# base-32-bit.net
KiCad netlist of a schematic drawn in Altium Designer
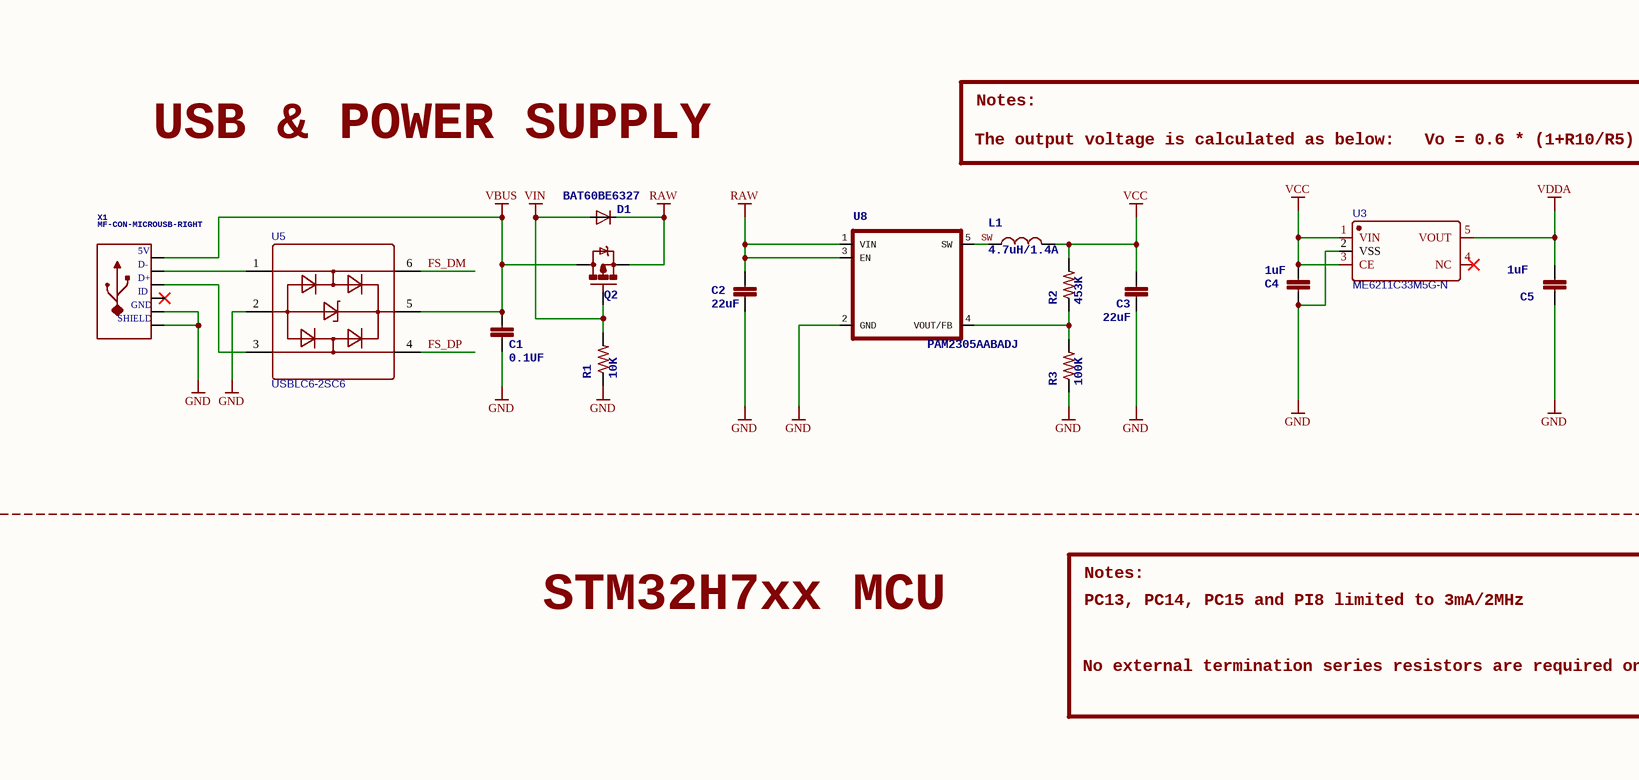
[diagram p0: base-32-bit.SchDoc, top left]
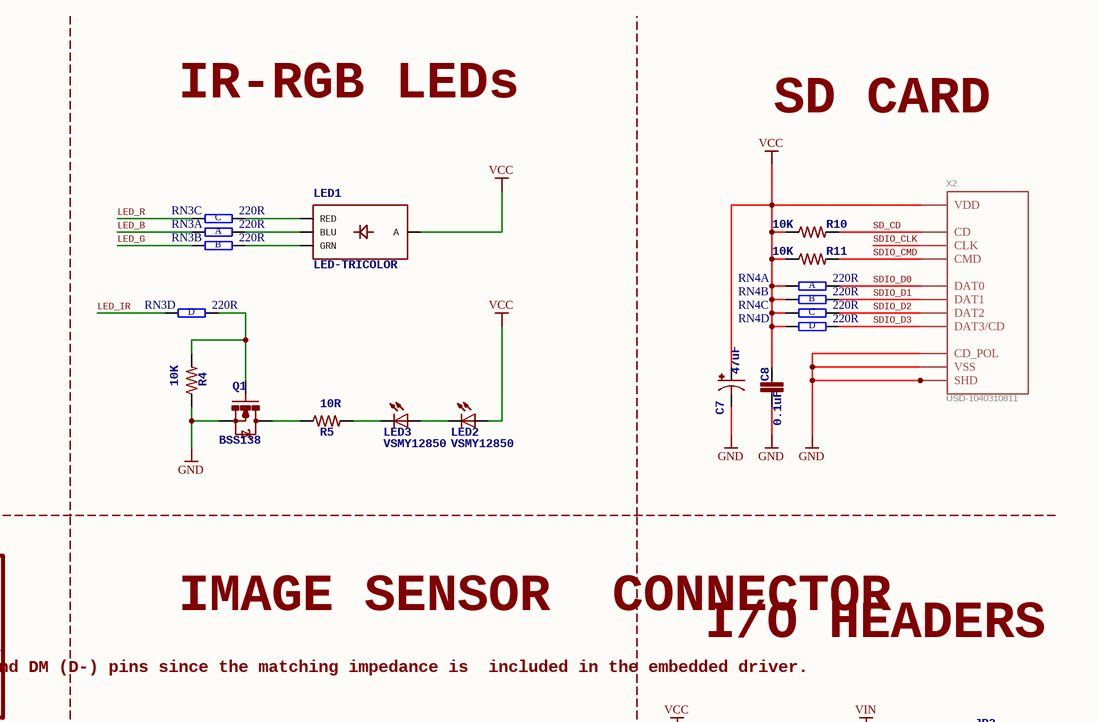
[diagram p1: base-32-bit.SchDoc, top right]
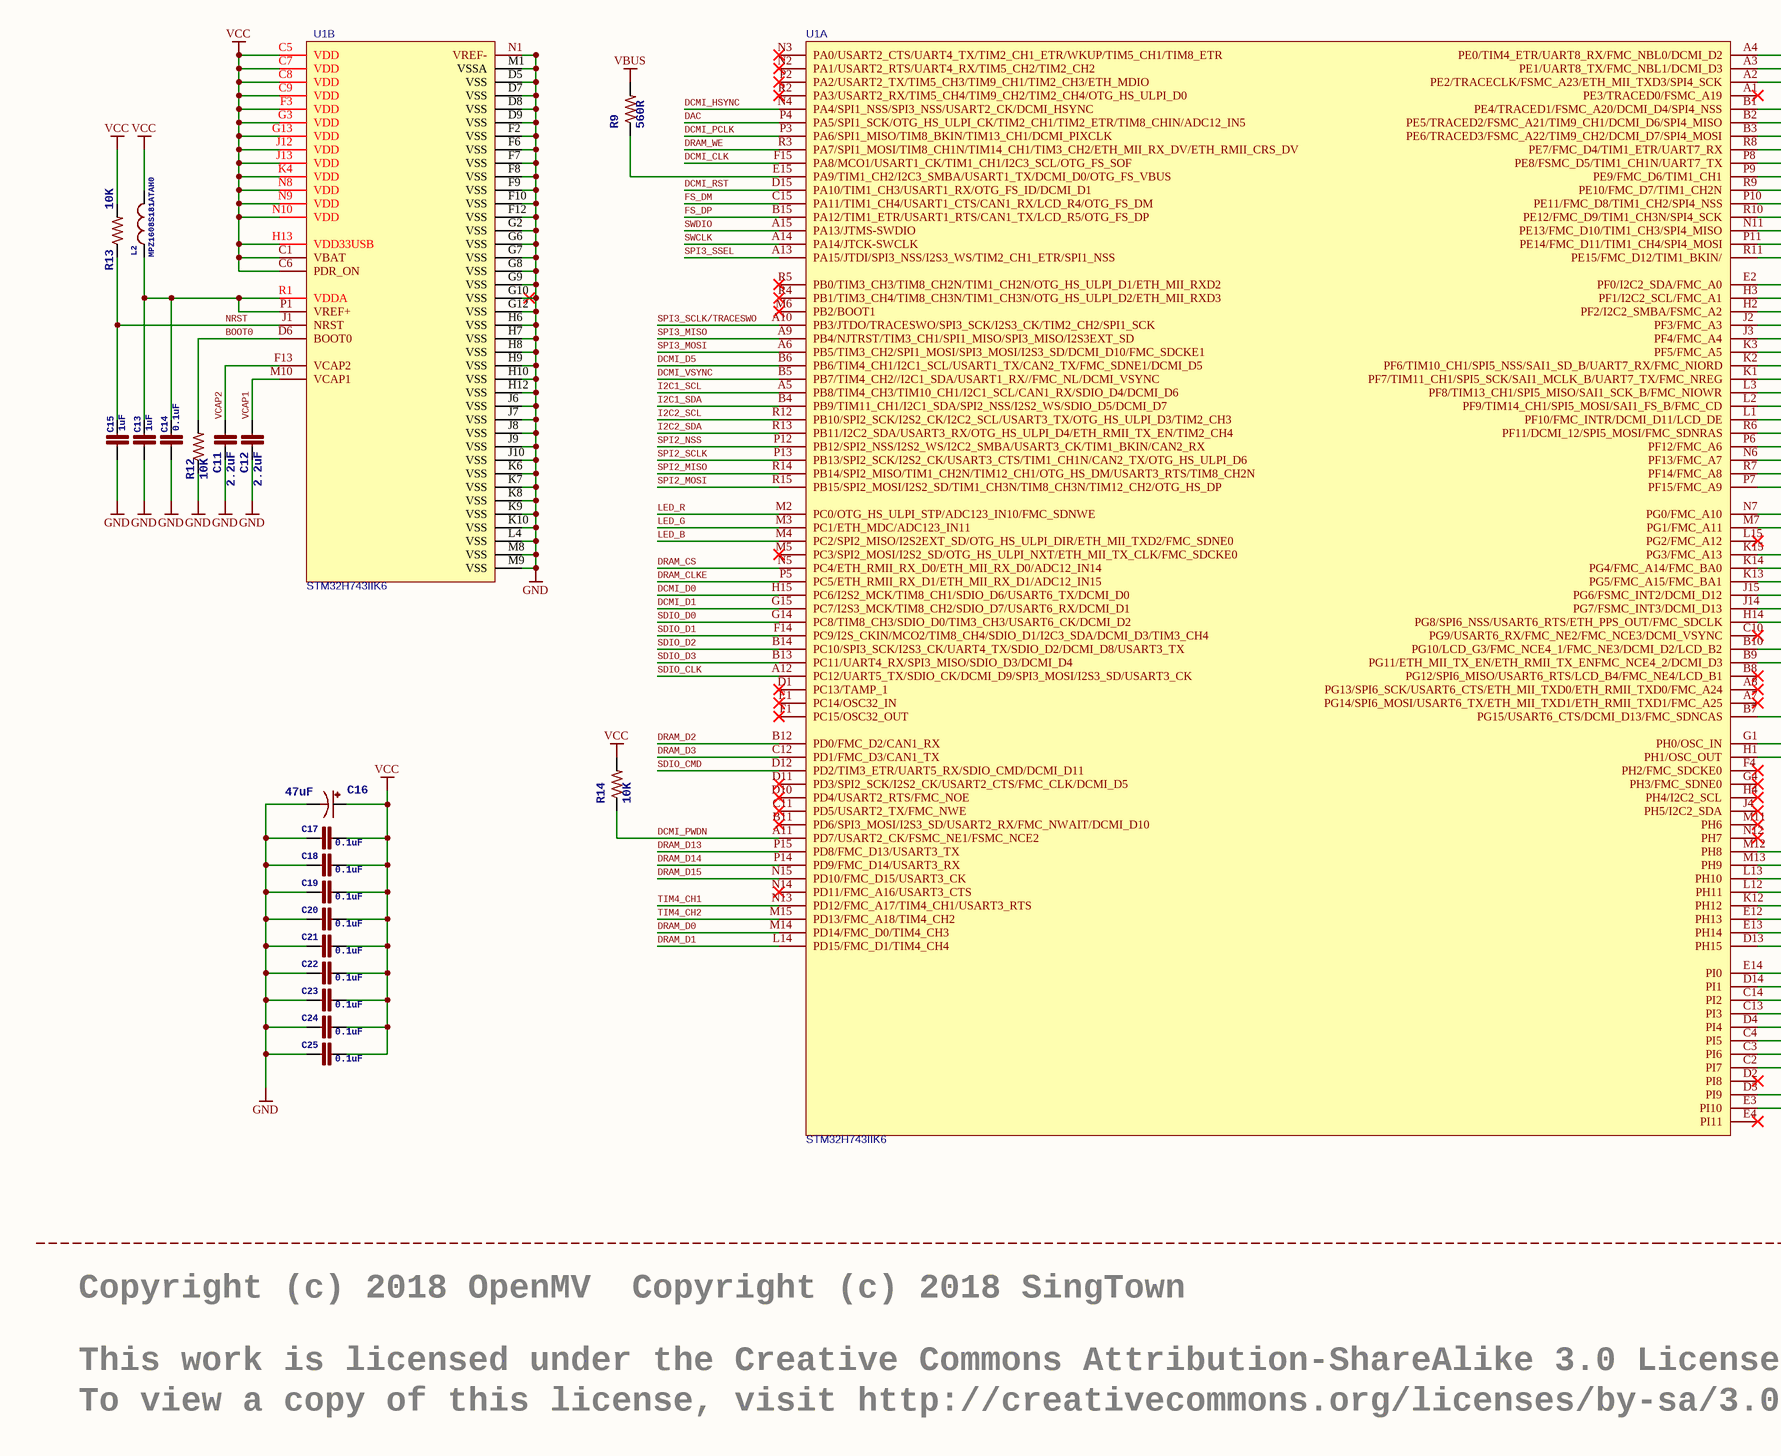
[diagram p2: base-32-bit.SchDoc, bottom left]
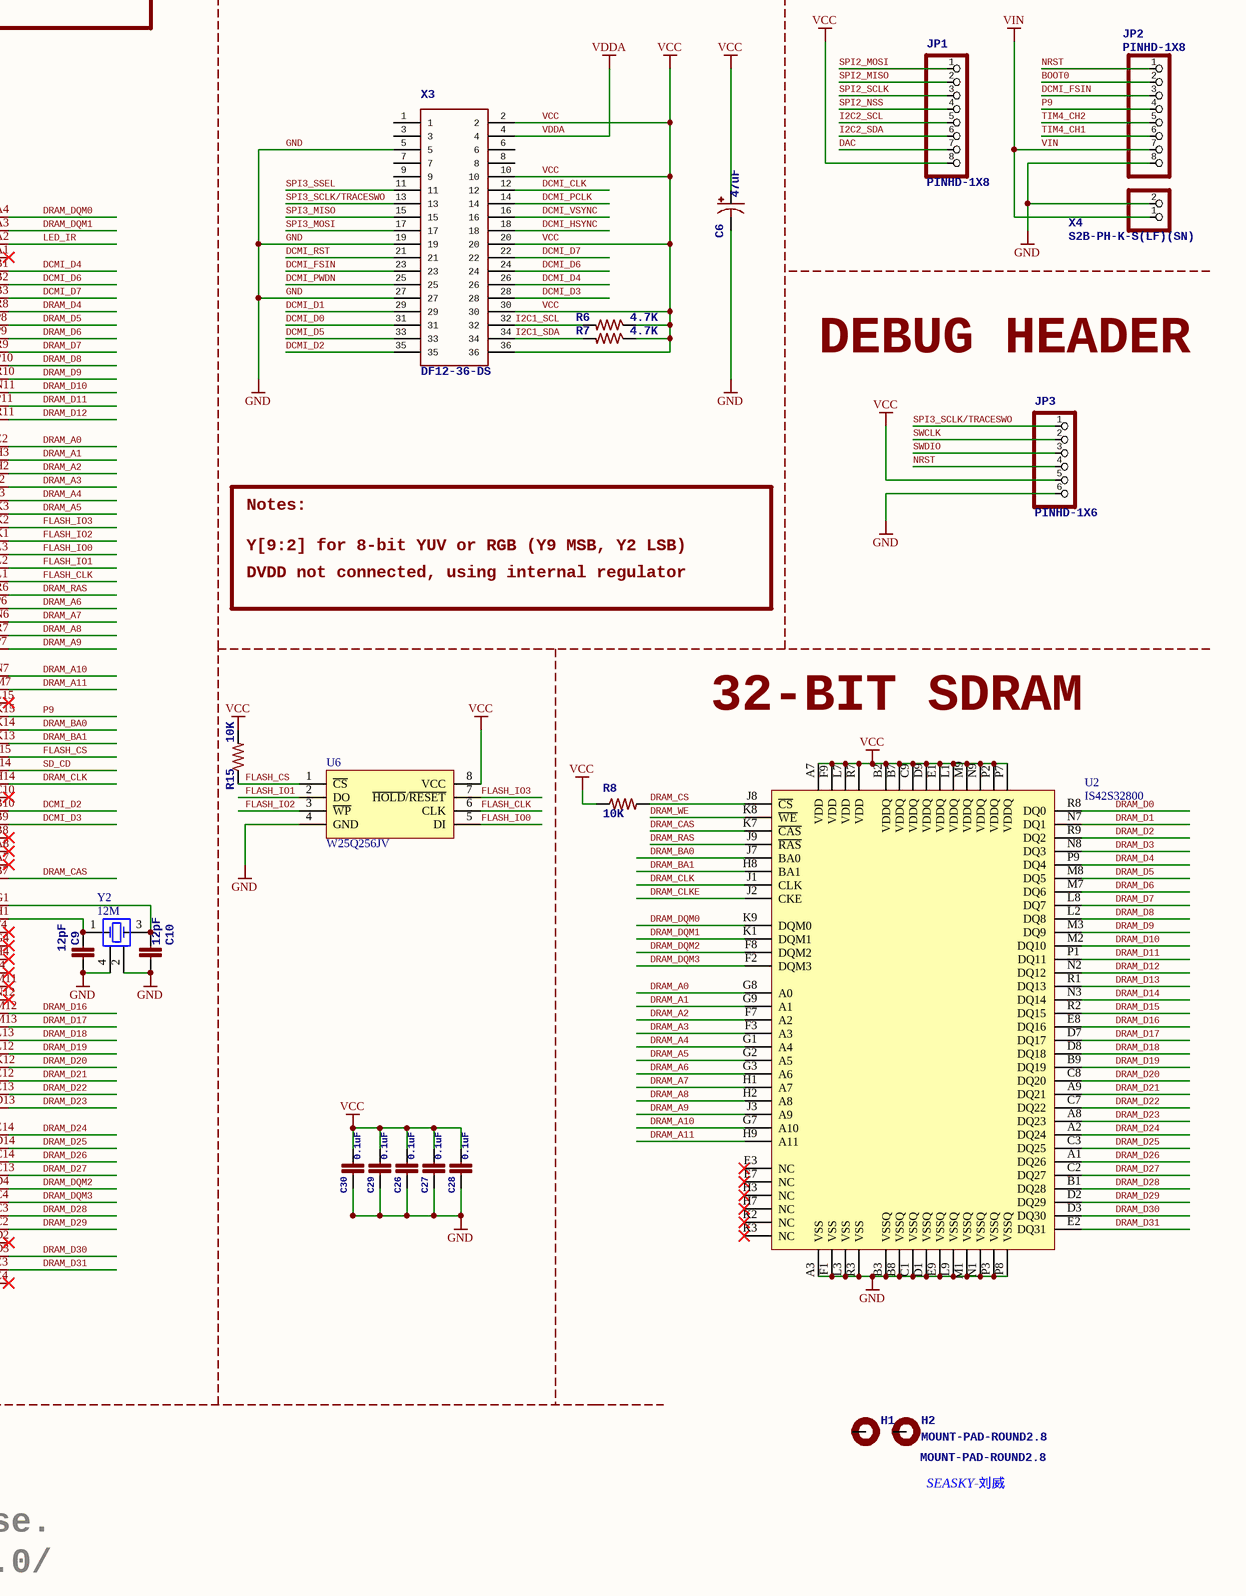
[diagram p3: base-32-bit.SchDoc, bottom right]

(export (version "E")
  (design (tool "Eeschema 10.0.6"))
  (components
    (comp (ref "C1")
      (value "0.1UF")
      (footprint "C0603")
      (description "CapacitorStandard 0603 ceramic capacitor, and 0.1\" leaded capacitor.")
      (libsource (lib "sfe") (part "CAP0805"))
    )
    (comp (ref "C2")
      (value "22uF")
      (footprint "0805")
      (description "CapacitorStandard 0603 ceramic capacitor, and 0.1\" leaded capacitor.")
      (libsource (lib "sfe") (part "CAP0805"))
    )
    (comp (ref "C3")
      (value "22uF")
      (footprint "0805")
      (description "CapacitorStandard 0603 ceramic capacitor, and 0.1\" leaded capacitor.")
      (libsource (lib "sfe") (part "CAP0805"))
    )
    (comp (ref "C4")
      (value "1uF")
      (footprint "0805")
      (description "CapacitorStandard 0603 ceramic capacitor, and 0.1\" leaded capacitor.")
      (libsource (lib "sfe") (part "CAP0805"))
    )
    (comp (ref "C5")
      (value "1uF")
      (footprint "0805")
      (description "CapacitorStandard 0603 ceramic capacitor, and 0.1\" leaded capacitor.")
      (libsource (lib "sfe") (part "CAP0805"))
    )
    (comp (ref "C6") (value "47uF") (footprint "EIA3216") (libsource (lib "") (part "CAP_POL1206_1")))
    (comp (ref "C7") (value "47uF") (footprint "EIA3216") (libsource (lib "") (part "CAP_POL1206_1")))
    (comp (ref "C8")
      (value "0.1uF")
      (footprint "0603-CAP")
      (description "CapacitorStandard 0603 ceramic capacitor, and 0.1\" leaded capacitor.")
      (libsource (lib "") (part "CAP0603-CAP_1"))
    )
    (comp (ref "C9")
      (value "12pF")
      (footprint "0603-CAP")
      (description "CapacitorStandard 0603 ceramic capacitor, and 0.1\" leaded capacitor.")
      (libsource (lib "sfe") (part "CAP0603-CAP"))
    )
    (comp (ref "C10")
      (value "12pF")
      (footprint "0603-CAP")
      (description "CapacitorStandard 0603 ceramic capacitor, and 0.1\" leaded capacitor.")
      (libsource (lib "sfe") (part "CAP0603-CAP"))
    )
    (comp (ref "C11")
      (value "2.2uF")
      (footprint "C0402")
      (description "CapacitorStandard 0603 ceramic capacitor, and 0.1\" leaded capacitor.")
      (libsource (lib "") (part "CAP0603-CAP_1"))
    )
    (comp (ref "C12")
      (value "2.2uF")
      (footprint "C0402")
      (description "CapacitorStandard 0603 ceramic capacitor, and 0.1\" leaded capacitor.")
      (libsource (lib "") (part "CAP0603-CAP_1"))
    )
    (comp (ref "C13")
      (value "1uF")
      (footprint "C0402")
      (description "CapacitorStandard 0603 ceramic capacitor, and 0.1\" leaded capacitor.")
      (libsource (lib "") (part "CAP0402-CAP_1"))
    )
    (comp (ref "C14")
      (value "0.1uF")
      (footprint "C0402")
      (description "CapacitorStandard 0603 ceramic capacitor, and 0.1\" leaded capacitor.")
      (libsource (lib "") (part "CAP0402-CAP_1"))
    )
    (comp (ref "C15")
      (value "1uF")
      (footprint "C0402")
      (description "CapacitorStandard 0603 ceramic capacitor, and 0.1\" leaded capacitor.")
      (libsource (lib "") (part "CAP0402-CAP_1"))
    )
    (comp (ref "C16") (value "47uF") (footprint "EIA3216") (libsource (lib "sfe") (part "CAP_POL1206")))
    (comp (ref "C17")
      (value "0.1uF")
      (footprint "C0402")
      (description "CapacitorStandard 0603 ceramic capacitor, and 0.1\" leaded capacitor.")
      (libsource (lib "sfe") (part "CAP0402-CAP"))
    )
    (comp (ref "C18")
      (value "0.1uF")
      (footprint "C0402")
      (description "CapacitorStandard 0603 ceramic capacitor, and 0.1\" leaded capacitor.")
      (libsource (lib "sfe") (part "CAP0402-CAP"))
    )
    (comp (ref "C19")
      (value "0.1uF")
      (footprint "C0402")
      (description "CapacitorStandard 0603 ceramic capacitor, and 0.1\" leaded capacitor.")
      (libsource (lib "sfe") (part "CAP0402-CAP"))
    )
    (comp (ref "C20")
      (value "0.1uF")
      (footprint "C0402")
      (description "CapacitorStandard 0603 ceramic capacitor, and 0.1\" leaded capacitor.")
      (libsource (lib "sfe") (part "CAP0402-CAP"))
    )
    (comp (ref "C21")
      (value "0.1uF")
      (footprint "C0402")
      (description "CapacitorStandard 0603 ceramic capacitor, and 0.1\" leaded capacitor.")
      (libsource (lib "sfe") (part "CAP0402-CAP"))
    )
    (comp (ref "C22")
      (value "0.1uF")
      (footprint "C0402")
      (description "CapacitorStandard 0603 ceramic capacitor, and 0.1\" leaded capacitor.")
      (libsource (lib "sfe") (part "CAP0402-CAP"))
    )
    (comp (ref "C23")
      (value "0.1uF")
      (footprint "C0402")
      (description "CapacitorStandard 0603 ceramic capacitor, and 0.1\" leaded capacitor.")
      (libsource (lib "sfe") (part "CAP0402-CAP"))
    )
    (comp (ref "C24")
      (value "0.1uF")
      (footprint "C0402")
      (description "CapacitorStandard 0603 ceramic capacitor, and 0.1\" leaded capacitor.")
      (libsource (lib "sfe") (part "CAP0402-CAP"))
    )
    (comp (ref "C25")
      (value "0.1uF")
      (footprint "C0402")
      (description "CapacitorStandard 0603 ceramic capacitor, and 0.1\" leaded capacitor.")
      (libsource (lib "sfe") (part "CAP0402-CAP"))
    )
    (comp (ref "C26")
      (value "0.1uF")
      (footprint "C0402")
      (description "CapacitorStandard 0603 ceramic capacitor, and 0.1\" leaded capacitor.")
      (libsource (lib "") (part "CAP0402-CAP_1"))
    )
    (comp (ref "C27")
      (value "0.1uF")
      (footprint "C0402")
      (description "CapacitorStandard 0603 ceramic capacitor, and 0.1\" leaded capacitor.")
      (libsource (lib "") (part "CAP0402-CAP_1"))
    )
    (comp (ref "C28")
      (value "0.1uF")
      (footprint "C0402")
      (description "CapacitorStandard 0603 ceramic capacitor, and 0.1\" leaded capacitor.")
      (libsource (lib "") (part "CAP0402-CAP_1"))
    )
    (comp (ref "C29")
      (value "0.1uF")
      (footprint "C0402")
      (description "CapacitorStandard 0603 ceramic capacitor, and 0.1\" leaded capacitor.")
      (libsource (lib "") (part "CAP0402-CAP_1"))
    )
    (comp (ref "C30")
      (value "0.1uF")
      (footprint "C0402")
      (description "CapacitorStandard 0603 ceramic capacitor, and 0.1\" leaded capacitor.")
      (libsource (lib "") (part "CAP0402-CAP_1"))
    )
    (comp (ref "D1") (value "BAT60BE6327") (footprint "SOD-323") (libsource (lib "sfe") (part "DIODESOD")))
    (comp (ref "H1")
      (value "MOUNT-PAD-ROUND2.8")
      (footprint "2,8-PAD")
      (description "MOUNTING PAD, round")
      (libsource (lib "holes") (part "MOUNT-PAD-ROUND2.8"))
    )
    (comp (ref "H2")
      (value "MOUNT-PAD-ROUND2.8")
      (footprint "2,8-PAD")
      (description "MOUNTING PAD, round")
      (libsource (lib "holes") (part "MOUNT-PAD-ROUND2.8"))
    )
    (comp (ref "JP1")
      (value "PINHD-1X8")
      (footprint "1X08")
      (description "PIN HEADER")
      (libsource (lib "pinhead") (part "PINHD-1X8"))
    )
    (comp (ref "JP2")
      (value "PINHD-1X8")
      (footprint "1X08")
      (description "PIN HEADER")
      (libsource (lib "pinhead") (part "PINHD-1X8"))
    )
    (comp (ref "JP3")
      (value "PINHD-1X6")
      (footprint "1X06")
      (description "PIN HEADER")
      (libsource (lib "pinhead") (part "PINHD-1X6"))
    )
    (comp (ref "L1") (value "4.7uH/1.4A") (footprint "1007") (libsource (lib "sfe") (part "INDUCTOR1007")))
    (comp (ref "L2")
      (value "MPZ1608S181ATAH0")
      (footprint "0603")
      (libsource (lib "sfe") (part "INDUCTOR0603"))
    )
    (comp (ref "LED1")
      (value "LED-TRICOLOR")
      (footprint "LED-TRICOLOR-SMD")
      (libsource (lib "sfe") (part "LED-TRICOLOR"))
    )
    (comp (ref "LED2") (value "VSMY12850") (footprint "LED-1206") (libsource (lib "sfe") (part "LED1206")))
    (comp (ref "LED3") (value "VSMY12850") (footprint "LED-1206") (libsource (lib "sfe") (part "LED1206")))
    (comp (ref "Q1")
      (value "BSS138")
      (footprint "SOT23-3")
      (libsource (lib "sfe") (part "MOSFET-NCHANNELSMD"))
    )
    (comp (ref "Q2")
      (value "Si2301BDS")
      (footprint "SOT23-3")
      (libsource (lib "sfe") (part "MOSFET-PCHANNELSMD"))
    )
    (comp (ref "R1")
      (value "10K")
      (footprint "R0603")
      (description "ResistorBasic schematic elements and footprints for 0603, 1206, and PTH resistors.")
      (libsource (lib "sfe") (part "RESISTOR0603-RES"))
    )
    (comp (ref "R2")
      (value "453K")
      (footprint "R0603")
      (description "ResistorBasic schematic elements and footprints for 0603, 1206, and PTH resistors.")
      (libsource (lib "sfe") (part "RESISTOR0603-RES"))
    )
    (comp (ref "R3")
      (value "100K")
      (footprint "R0603")
      (description "ResistorBasic schematic elements and footprints for 0603, 1206, and PTH resistors.")
      (libsource (lib "sfe") (part "RESISTOR0603-RES"))
    )
    (comp (ref "R4")
      (value "10K")
      (footprint "R0603")
      (description "ResistorBasic schematic elements and footprints for 0603, 1206, and PTH resistors.")
      (libsource (lib "sfe") (part "RESISTOR0603-RES"))
    )
    (comp (ref "R5")
      (value "10R")
      (footprint "R0603")
      (description "ResistorBasic schematic elements and footprints for 0603, 1206, and PTH resistors.")
      (libsource (lib "sfe") (part "RESISTOR0603-RES"))
    )
    (comp (ref "R6")
      (value "4.7K")
      (footprint "R0603")
      (description "ResistorBasic schematic elements and footprints for 0603, 1206, and PTH resistors.")
      (libsource (lib "sfe") (part "RESISTOR0603-RES"))
    )
    (comp (ref "R7")
      (value "4.7K")
      (footprint "R0603")
      (description "ResistorBasic schematic elements and footprints for 0603, 1206, and PTH resistors.")
      (libsource (lib "sfe") (part "RESISTOR0603-RES"))
    )
    (comp (ref "R8")
      (value "10K")
      (footprint "R0402")
      (description "ResistorBasic schematic elements and footprints for 0603, 1206, and PTH resistors.")
      (libsource (lib "sfe") (part "RESISTOR0402-RES"))
    )
    (comp (ref "R9")
      (value "560R")
      (footprint "R0603")
      (description "ResistorBasic schematic elements and footprints for 0603, 1206, and PTH resistors.")
      (libsource (lib "sfe") (part "RESISTOR0603-RES"))
    )
    (comp (ref "R10")
      (value "10K")
      (footprint "R0603")
      (description "ResistorBasic schematic elements and footprints for 0603, 1206, and PTH resistors.")
      (libsource (lib "sfe") (part "RESISTOR0603-RES"))
    )
    (comp (ref "R11")
      (value "10K")
      (footprint "R0603")
      (description "ResistorBasic schematic elements and footprints for 0603, 1206, and PTH resistors.")
      (libsource (lib "sfe") (part "RESISTOR0603-RES"))
    )
    (comp (ref "R12")
      (value "10K")
      (footprint "R0603")
      (description "ResistorBasic schematic elements and footprints for 0603, 1206, and PTH resistors.")
      (libsource (lib "sfe") (part "RESISTOR0603-RES"))
    )
    (comp (ref "R13")
      (value "10K")
      (footprint "R0402")
      (description "ResistorBasic schematic elements and footprints for 0603, 1206, and PTH resistors.")
      (libsource (lib "sfe") (part "RESISTOR0603-RES"))
    )
    (comp (ref "R14")
      (value "10K")
      (footprint "R0603")
      (description "ResistorBasic schematic elements and footprints for 0603, 1206, and PTH resistors.")
      (libsource (lib "sfe") (part "RESISTOR0603-RES"))
    )
    (comp (ref "R15")
      (value "10K")
      (footprint "R0603")
      (description "ResistorBasic schematic elements and footprints for 0603, 1206, and PTH resistors.")
      (libsource (lib "sfe") (part "RESISTOR0402-RES"))
    )
    (comp (ref "RN3")
      (value "220R")
      (footprint "RCA-8P4R-0402")
      (libsource (lib "Integrated_Library1") (part "排阻_4P"))
    )
    (comp (ref "RN4")
      (value "220R")
      (footprint "RCA-8P4R-0402")
      (libsource (lib "Integrated_Library1") (part "排阻_4P"))
    )
    (comp (ref "U1")
      (value "STM32H743IIK6")
      (footprint "UFBGA-201_L10.0-W10.0-P0.65-TL_STM32H743IIK6")
      (fields
        (field (name "BOM_SUPPLIER PART") "C129442")
        (field (name "SUBPART_NO") "2")
        (field (name "CONTRIBUTOR") "LCSC")
      )
      (libsource (lib "Integrated_Library1") (part "STM32H743IIK6"))
    )
    (comp (ref "U2")
      (value "IS42S32800")
      (footprint "BGA-90-8000X13000DE")
      (libsource (lib "Schlib1") (part "IS42S32800"))
    )
    (comp (ref "U3")
      (value "ME6211C33M5G-N")
      (footprint "SOT-23-5")
      (fields (field (name "BOM_SUPPLIER PART") "C82942"))
      (libsource (lib "Integrated_Library1") (part "ME6211C33M5G-N"))
    )
    (comp (ref "U5")
      (value "USBLC6-2SC6")
      (footprint "SOT-23-6")
      (fields (field (name "BOM_SUPPLIER PART") "C7519"))
      (libsource (lib "Integrated_Library1") (part "USBLC6-2SC6"))
    )
    (comp (ref "U6")
      (value "W25Q256JV")
      (footprint "WSON-8_L8.0-W6.10-P1.27-BL-EP")
      (libsource (lib "Integrated_Library1") (part "W25Q128JVSQ"))
    )
    (comp (ref "U8")
      (value "PAM2305AABADJ")
      (footprint "TSOT25")
      (libsource (lib "regulators") (part "PAM2305AAB330"))
    )
    (comp (ref "X1")
      (value "MF-CON-MICROUSB-RIGHT")
      (footprint "MICROUSB-RIGHT")
      (libsource (lib "base-16-bit") (part "USB_MICRO_RIGHT"))
    )
    (comp (ref "X2")
      (value "USD-1040310811")
      (footprint "1040310811")
      (libsource (lib "base-32-bit") (part "USD-1040310811"))
    )
    (comp (ref "X3")
      (value "DF12-36-DS")
      (footprint "DF12-36-DS")
      (libsource (lib "DF12") (part "DF12-36-DS"))
    )
    (comp (ref "X4")
      (value "S2B-PH-K-S(LF)(SN)")
      (footprint "JST-PH-2-THM-RA")
      (libsource (lib "adafruit-updated") (part "JST_2PIN-THM-RA"))
    )
    (comp (ref "Y2")
      (value "12M")
      (footprint "OSC-SMD_4P-L2.5-W2.0-BL")
      (libsource (lib "wwwmcucn_sch") (part "XTAL-NV-4"))
    )
  )
  (nets
    (net (code "1") (name "/BOOT0") (class "Default")
      (node (ref "JP2") (pin "2") (pinfunction "2_2") (pintype "passive"))
      (node (ref "R12") (pin "2") (pinfunction "2_2") (pintype "passive"))
      (node (ref "U1") (pin "D6") (pinfunction "BOOT0_D6") (pintype "passive"))
    )
    (net (code "2") (name "/DAC") (class "Default")
      (node (ref "JP1") (pin "7") (pinfunction "7_7") (pintype "passive"))
      (node (ref "U1") (pin "P4") (pinfunction "PA5/SPI1_SCK/OTG_HS_ULPI_CK/TIM2_CH1/TIM2_ETR/TIM8_CHIN/ADC12_IN5_P4") (pintype "passive"))
    )
    (net (code "3") (name "/DCMI_CLK") (class "Default")
      (node (ref "U1") (pin "F15") (pinfunction "PA8/MCO1/USART1_CK/TIM1_CH1/I2C3_SCL/OTG_FS_SOF_F15") (pintype "passive"))
      (node (ref "X3") (pin "12") (pinfunction "12_12") (pintype "passive"))
    )
    (net (code "4") (name "/DCMI_D0") (class "Default")
      (node (ref "U1") (pin "H15") (pinfunction "PC6/I2S2_MCK/TIM8_CH1/SDIO_D6/USART6_TX/DCMI_D0_H15") (pintype "passive"))
      (node (ref "X3") (pin "31") (pinfunction "31_31") (pintype "passive"))
    )
    (net (code "5") (name "/DCMI_D1") (class "Default")
      (node (ref "U1") (pin "G15") (pinfunction "PC7/I2S3_MCK/TIM8_CH2/SDIO_D7/USART6_RX/DCMI_D1_G15") (pintype "passive"))
      (node (ref "X3") (pin "29") (pinfunction "29_29") (pintype "passive"))
    )
    (net (code "6") (name "/DCMI_D2") (class "Default")
      (node (ref "U1") (pin "B10") (pinfunction "PG10/LCD_G3/FMC_NCE4_1/FMC_NE3/DCMI_D2/LCD_B2_B10") (pintype "passive"))
      (node (ref "X3") (pin "35") (pinfunction "35_35") (pintype "passive"))
    )
    (net (code "7") (name "/DCMI_D3") (class "Default")
      (node (ref "U1") (pin "B9") (pinfunction "PG11/ETH_MII_TX_EN/ETH_RMII_TX_ENFMC_NCE4_2/DCMI_D3_B9") (pintype "passive"))
      (node (ref "X3") (pin "28") (pinfunction "28_28") (pintype "passive"))
    )
    (net (code "8") (name "/DCMI_D4") (class "Default")
      (node (ref "U1") (pin "B1") (pinfunction "PE4/TRACED1/FSMC_A20/DCMI_D4/SPI4_NSS_B1") (pintype "passive"))
      (node (ref "X3") (pin "26") (pinfunction "26_26") (pintype "passive"))
    )
    (net (code "9") (name "/DCMI_D5") (class "Default")
      (node (ref "U1") (pin "B6") (pinfunction "PB6/TIM4_CH1/I2C1_SCL/USART1_TX/CAN2_TX/FMC_SDNE1/DCMI_D5_B6") (pintype "passive"))
      (node (ref "X3") (pin "33") (pinfunction "33_33") (pintype "passive"))
    )
    (net (code "10") (name "/DCMI_D6") (class "Default")
      (node (ref "U1") (pin "B2") (pinfunction "PE5/TRACED2/FSMC_A21/TIM9_CH1/DCMI_D6/SPI4_MISO_B2") (pintype "passive"))
      (node (ref "X3") (pin "24") (pinfunction "24_24") (pintype "passive"))
    )
    (net (code "11") (name "/DCMI_D7") (class "Default")
      (node (ref "U1") (pin "B3") (pinfunction "PE6/TRACED3/FSMC_A22/TIM9_CH2/DCMI_D7/SPI4_MOSI_B3") (pintype "passive"))
      (node (ref "X3") (pin "22") (pinfunction "22_22") (pintype "passive"))
    )
    (net (code "12") (name "/DCMI_FSIN") (class "Default")
      (node (ref "JP2") (pin "3") (pinfunction "3_3") (pintype "passive"))
      (node (ref "X3") (pin "23") (pinfunction "23_23") (pintype "passive"))
    )
    (net (code "13") (name "/DCMI_HSYNC") (class "Default")
      (node (ref "U1") (pin "N4") (pinfunction "PA4/SPI1_NSS/SPI3_NSS/USART2_CK/DCMI_HSYNC_N4") (pintype "passive"))
      (node (ref "X3") (pin "18") (pinfunction "18_18") (pintype "passive"))
    )
    (net (code "14") (name "/DCMI_PCLK") (class "Default")
      (node (ref "U1") (pin "P3") (pinfunction "PA6/SPI1_MISO/TIM8_BKIN/TIM13_CH1/DCMI_PIXCLK_P3") (pintype "passive"))
      (node (ref "X3") (pin "14") (pinfunction "14_14") (pintype "passive"))
    )
    (net (code "15") (name "/DCMI_PWDN") (class "Default")
      (node (ref "R14") (pin "1") (pinfunction "1_1") (pintype "passive"))
      (node (ref "U1") (pin "A11") (pinfunction "PD7/USART2_CK/FSMC_NE1/FSMC_NCE2_A11") (pintype "passive"))
      (node (ref "X3") (pin "25") (pinfunction "25_25") (pintype "passive"))
    )
    (net (code "16") (name "/DCMI_RST") (class "Default")
      (node (ref "U1") (pin "D15") (pinfunction "PA10/TIM1_CH3/USART1_RX/OTG_FS_ID/DCMI_D1_D15") (pintype "passive"))
      (node (ref "X3") (pin "21") (pinfunction "21_21") (pintype "passive"))
    )
    (net (code "17") (name "/DCMI_VSYNC") (class "Default")
      (node (ref "U1") (pin "B5") (pinfunction "PB7/TIM4_CH2//I2C1_SDA/USART1_RX//FMC_NL/DCMI_VSYNC_B5") (pintype "passive"))
      (node (ref "X3") (pin "16") (pinfunction "16_16") (pintype "passive"))
    )
    (net (code "18") (name "/DRAM_A0") (class "Default")
      (node (ref "U1") (pin "E2") (pinfunction "PF0/I2C2_SDA/FMC_A0_E2") (pintype "passive"))
      (node (ref "U2") (pin "G8") (pinfunction "A0_G8") (pintype "passive"))
    )
    (net (code "19") (name "/DRAM_A1") (class "Default")
      (node (ref "U1") (pin "H3") (pinfunction "PF1/I2C2_SCL/FMC_A1_H3") (pintype "passive"))
      (node (ref "U2") (pin "G9") (pinfunction "A1_G9") (pintype "passive"))
    )
    (net (code "20") (name "/DRAM_A2") (class "Default")
      (node (ref "U1") (pin "H2") (pinfunction "PF2/I2C2_SMBA/FSMC_A2_H2") (pintype "passive"))
      (node (ref "U2") (pin "F7") (pinfunction "A2_F7") (pintype "passive"))
    )
    (net (code "21") (name "/DRAM_A3") (class "Default")
      (node (ref "U1") (pin "J2") (pinfunction "PF3/FMC_A3_J2") (pintype "passive"))
      (node (ref "U2") (pin "F3") (pinfunction "A3_F3") (pintype "passive"))
    )
    (net (code "22") (name "/DRAM_A4") (class "Default")
      (node (ref "U1") (pin "J3") (pinfunction "PF4/FMC_A4_J3") (pintype "passive"))
      (node (ref "U2") (pin "G1") (pinfunction "A4_G1") (pintype "passive"))
    )
    (net (code "23") (name "/DRAM_A5") (class "Default")
      (node (ref "U1") (pin "K3") (pinfunction "PF5/FMC_A5_K3") (pintype "passive"))
      (node (ref "U2") (pin "G2") (pinfunction "A5_G2") (pintype "passive"))
    )
    (net (code "24") (name "/DRAM_A6") (class "Default")
      (node (ref "U1") (pin "P6") (pinfunction "PF12/FMC_A6_P6") (pintype "passive"))
      (node (ref "U2") (pin "G3") (pinfunction "A6_G3") (pintype "passive"))
    )
    (net (code "25") (name "/DRAM_A7") (class "Default")
      (node (ref "U1") (pin "N6") (pinfunction "PF13/FMC_A7_N6") (pintype "passive"))
      (node (ref "U2") (pin "H1") (pinfunction "A7_H1") (pintype "passive"))
    )
    (net (code "26") (name "/DRAM_A8") (class "Default")
      (node (ref "U1") (pin "R7") (pinfunction "PF14/FMC_A8_R7") (pintype "passive"))
      (node (ref "U2") (pin "H2") (pinfunction "A8_H2") (pintype "passive"))
    )
    (net (code "27") (name "/DRAM_A9") (class "Default")
      (node (ref "U1") (pin "P7") (pinfunction "PF15/FMC_A9_P7") (pintype "passive"))
      (node (ref "U2") (pin "J3") (pinfunction "A9_J3") (pintype "passive"))
    )
    (net (code "28") (name "/DRAM_A10") (class "Default")
      (node (ref "U1") (pin "N7") (pinfunction "PG0/FMC_A10_N7") (pintype "passive"))
      (node (ref "U2") (pin "G7") (pinfunction "A10_G7") (pintype "passive"))
    )
    (net (code "29") (name "/DRAM_A11") (class "Default")
      (node (ref "U1") (pin "M7") (pinfunction "PG1/FMC_A11_M7") (pintype "passive"))
      (node (ref "U2") (pin "H9") (pinfunction "A11_H9") (pintype "passive"))
    )
    (net (code "30") (name "/DRAM_BA0") (class "Default")
      (node (ref "U1") (pin "K14") (pinfunction "PG4/FMC_A14/FMC_BA0_K14") (pintype "passive"))
      (node (ref "U2") (pin "J7") (pinfunction "BA0_J7") (pintype "passive"))
    )
    (net (code "31") (name "/DRAM_BA1") (class "Default")
      (node (ref "U1") (pin "K13") (pinfunction "PG5/FMC_A15/FMC_BA1_K13") (pintype "passive"))
      (node (ref "U2") (pin "H8") (pinfunction "BA1_H8") (pintype "passive"))
    )
    (net (code "32") (name "/DRAM_CAS") (class "Default")
      (node (ref "U1") (pin "B7") (pinfunction "PG15/USART6_CTS/DCMI_D13/FMC_SDNCAS_B7") (pintype "passive"))
      (node (ref "U2") (pin "K7") (pinfunction "~{CAS}_K7") (pintype "passive"))
    )
    (net (code "33") (name "/DRAM_CLK") (class "Default")
      (node (ref "U1") (pin "H14") (pinfunction "PG8/SPI6_NSS/USART6_RTS/ETH_PPS_OUT/FMC_SDCLK_H14") (pintype "passive"))
      (node (ref "U2") (pin "J1") (pinfunction "CLK_J1") (pintype "passive"))
    )
    (net (code "34") (name "/DRAM_CLKE") (class "Default")
      (node (ref "U1") (pin "P5") (pinfunction "PC5/ETH_RMII_RX_D1/ETH_MII_RX_D1/ADC12_IN15_P5") (pintype "passive"))
      (node (ref "U2") (pin "J2") (pinfunction "CKE_J2") (pintype "passive"))
    )
    (net (code "35") (name "/DRAM_CS") (class "Default")
      (node (ref "R8") (pin "2") (pinfunction "2_2") (pintype "passive"))
      (node (ref "U1") (pin "N5") (pinfunction "PC4/ETH_RMII_RX_D0/ETH_MII_RX_D0/ADC12_IN14_N5") (pintype "passive"))
      (node (ref "U2") (pin "J8") (pinfunction "~{CS}_J8") (pintype "passive"))
    )
    (net (code "36") (name "/DRAM_D0") (class "Default")
      (node (ref "U1") (pin "M14") (pinfunction "PD14/FMC_D0/TIM4_CH3_M14") (pintype "passive"))
      (node (ref "U2") (pin "R8") (pinfunction "DQ0_R8") (pintype "passive"))
    )
    (net (code "37") (name "/DRAM_D1") (class "Default")
      (node (ref "U1") (pin "L14") (pinfunction "PD15/FMC_D1/TIM4_CH4_L14") (pintype "passive"))
      (node (ref "U2") (pin "N7") (pinfunction "DQ1_N7") (pintype "passive"))
    )
    (net (code "38") (name "/DRAM_D2") (class "Default")
      (node (ref "U1") (pin "B12") (pinfunction "PD0/FMC_D2/CAN1_RX_B12") (pintype "passive"))
      (node (ref "U2") (pin "R9") (pinfunction "DQ2_R9") (pintype "passive"))
    )
    (net (code "39") (name "/DRAM_D3") (class "Default")
      (node (ref "U1") (pin "C12") (pinfunction "PD1/FMC_D3/CAN1_TX_C12") (pintype "passive"))
      (node (ref "U2") (pin "N8") (pinfunction "DQ3_N8") (pintype "passive"))
    )
    (net (code "40") (name "/DRAM_D4") (class "Default")
      (node (ref "U1") (pin "R8") (pinfunction "PE7/FMC_D4/TIM1_ETR/UART7_RX_R8") (pintype "passive"))
      (node (ref "U2") (pin "P9") (pinfunction "DQ4_P9") (pintype "passive"))
    )
    (net (code "41") (name "/DRAM_D5") (class "Default")
      (node (ref "U1") (pin "P8") (pinfunction "PE8/FSMC_D5/TIM1_CH1N/UART7_TX_P8") (pintype "passive"))
      (node (ref "U2") (pin "M8") (pinfunction "DQ5_M8") (pintype "passive"))
    )
    (net (code "42") (name "/DRAM_D6") (class "Default")
      (node (ref "U1") (pin "P9") (pinfunction "PE9/FMC_D6/TIM1_CH1_P9") (pintype "passive"))
      (node (ref "U2") (pin "M7") (pinfunction "DQ6_M7") (pintype "passive"))
    )
    (net (code "43") (name "/DRAM_D7") (class "Default")
      (node (ref "U1") (pin "R9") (pinfunction "PE10/FMC_D7/TIM1_CH2N_R9") (pintype "passive"))
      (node (ref "U2") (pin "L8") (pinfunction "DQ7_L8") (pintype "passive"))
    )
    (net (code "44") (name "/DRAM_D8") (class "Default")
      (node (ref "U1") (pin "P10") (pinfunction "PE11/FMC_D8/TIM1_CH2/SPI4_NSS_P10") (pintype "passive"))
      (node (ref "U2") (pin "L2") (pinfunction "DQ8_L2") (pintype "passive"))
    )
    (net (code "45") (name "/DRAM_D9") (class "Default")
      (node (ref "U1") (pin "R10") (pinfunction "PE12/FMC_D9/TIM1_CH3N/SPI4_SCK_R10") (pintype "passive"))
      (node (ref "U2") (pin "M3") (pinfunction "DQ9_M3") (pintype "passive"))
    )
    (net (code "46") (name "/DRAM_D10") (class "Default")
      (node (ref "U1") (pin "N11") (pinfunction "PE13/FMC_D10/TIM1_CH3/SPI4_MISO_N11") (pintype "passive"))
      (node (ref "U2") (pin "M2") (pinfunction "DQ10_M2") (pintype "passive"))
    )
    (net (code "47") (name "/DRAM_D11") (class "Default")
      (node (ref "U1") (pin "P11") (pinfunction "PE14/FMC_D11/TIM1_CH4/SPI4_MOSI_P11") (pintype "passive"))
      (node (ref "U2") (pin "P1") (pinfunction "DQ11_P1") (pintype "passive"))
    )
    (net (code "48") (name "/DRAM_D12") (class "Default")
      (node (ref "U1") (pin "R11") (pinfunction "PE15/FMC_D12/TIM1_BKIN/_R11") (pintype "passive"))
      (node (ref "U2") (pin "N2") (pinfunction "DQ12_N2") (pintype "passive"))
    )
    (net (code "49") (name "/DRAM_D13") (class "Default")
      (node (ref "U1") (pin "P15") (pinfunction "PD8/FMC_D13/USART3_TX_P15") (pintype "passive"))
      (node (ref "U2") (pin "R1") (pinfunction "DQ13_R1") (pintype "passive"))
    )
    (net (code "50") (name "/DRAM_D14") (class "Default")
      (node (ref "U1") (pin "P14") (pinfunction "PD9/FMC_D14/USART3_RX_P14") (pintype "passive"))
      (node (ref "U2") (pin "N3") (pinfunction "DQ14_N3") (pintype "passive"))
    )
    (net (code "51") (name "/DRAM_D15") (class "Default")
      (node (ref "U1") (pin "N15") (pinfunction "PD10/FMC_D15/USART3_CK_N15") (pintype "passive"))
      (node (ref "U2") (pin "R2") (pinfunction "DQ15_R2") (pintype "passive"))
    )
    (net (code "52") (name "/DRAM_D16") (class "Default")
      (node (ref "U1") (pin "M12") (pinfunction "PH8_M12") (pintype "passive"))
      (node (ref "U2") (pin "E8") (pinfunction "DQ16_E8") (pintype "passive"))
    )
    (net (code "53") (name "/DRAM_D17") (class "Default")
      (node (ref "U1") (pin "M13") (pinfunction "PH9_M13") (pintype "passive"))
      (node (ref "U2") (pin "D7") (pinfunction "DQ17_D7") (pintype "passive"))
    )
    (net (code "54") (name "/DRAM_D18") (class "Default")
      (node (ref "U1") (pin "L13") (pinfunction "PH10_L13") (pintype "passive"))
      (node (ref "U2") (pin "D8") (pinfunction "DQ18_D8") (pintype "passive"))
    )
    (net (code "55") (name "/DRAM_D19") (class "Default")
      (node (ref "U1") (pin "L12") (pinfunction "PH11_L12") (pintype "passive"))
      (node (ref "U2") (pin "B9") (pinfunction "DQ19_B9") (pintype "passive"))
    )
    (net (code "56") (name "/DRAM_D20") (class "Default")
      (node (ref "U1") (pin "K12") (pinfunction "PH12_K12") (pintype "passive"))
      (node (ref "U2") (pin "C8") (pinfunction "DQ20_C8") (pintype "passive"))
    )
    (net (code "57") (name "/DRAM_D21") (class "Default")
      (node (ref "U1") (pin "E12") (pinfunction "PH13_E12") (pintype "passive"))
      (node (ref "U2") (pin "A9") (pinfunction "DQ21_A9") (pintype "passive"))
    )
    (net (code "58") (name "/DRAM_D22") (class "Default")
      (node (ref "U1") (pin "E13") (pinfunction "PH14_E13") (pintype "passive"))
      (node (ref "U2") (pin "C7") (pinfunction "DQ22_C7") (pintype "passive"))
    )
    (net (code "59") (name "/DRAM_D23") (class "Default")
      (node (ref "U1") (pin "D13") (pinfunction "PH15_D13") (pintype "passive"))
      (node (ref "U2") (pin "A8") (pinfunction "DQ23_A8") (pintype "passive"))
    )
    (net (code "60") (name "/DRAM_D24") (class "Default")
      (node (ref "U1") (pin "E14") (pinfunction "PI0_E14") (pintype "passive"))
      (node (ref "U2") (pin "A2") (pinfunction "DQ24_A2") (pintype "passive"))
    )
    (net (code "61") (name "/DRAM_D25") (class "Default")
      (node (ref "U1") (pin "D14") (pinfunction "PI1_D14") (pintype "passive"))
      (node (ref "U2") (pin "C3") (pinfunction "DQ25_C3") (pintype "passive"))
    )
    (net (code "62") (name "/DRAM_D26") (class "Default")
      (node (ref "U1") (pin "C14") (pinfunction "PI2_C14") (pintype "passive"))
      (node (ref "U2") (pin "A1") (pinfunction "DQ26_A1") (pintype "passive"))
    )
    (net (code "63") (name "/DRAM_D27") (class "Default")
      (node (ref "U1") (pin "C13") (pinfunction "PI3_C13") (pintype "passive"))
      (node (ref "U2") (pin "C2") (pinfunction "DQ27_C2") (pintype "passive"))
    )
    (net (code "64") (name "/DRAM_D28") (class "Default")
      (node (ref "U1") (pin "C3") (pinfunction "PI6_C3") (pintype "passive"))
      (node (ref "U2") (pin "B1") (pinfunction "DQ28_B1") (pintype "passive"))
    )
    (net (code "65") (name "/DRAM_D29") (class "Default")
      (node (ref "U1") (pin "C2") (pinfunction "PI7_C2") (pintype "passive"))
      (node (ref "U2") (pin "D2") (pinfunction "DQ29_D2") (pintype "passive"))
    )
    (net (code "66") (name "/DRAM_D30") (class "Default")
      (node (ref "U1") (pin "D3") (pinfunction "PI9_D3") (pintype "passive"))
      (node (ref "U2") (pin "D3") (pinfunction "DQ30_D3") (pintype "passive"))
    )
    (net (code "67") (name "/DRAM_D31") (class "Default")
      (node (ref "U1") (pin "E3") (pinfunction "PI10_E3") (pintype "passive"))
      (node (ref "U2") (pin "E2") (pinfunction "DQ31_E2") (pintype "passive"))
    )
    (net (code "68") (name "/DRAM_DQM0") (class "Default")
      (node (ref "U1") (pin "A4") (pinfunction "PE0/TIM4_ETR/UART8_RX/FMC_NBL0/DCMI_D2_A4") (pintype "passive"))
      (node (ref "U2") (pin "K9") (pinfunction "DQM0_K9") (pintype "passive"))
    )
    (net (code "69") (name "/DRAM_DQM1") (class "Default")
      (node (ref "U1") (pin "A3") (pinfunction "PE1/UART8_TX/FMC_NBL1/DCMI_D3_A3") (pintype "passive"))
      (node (ref "U2") (pin "K1") (pinfunction "DQM1_K1") (pintype "passive"))
    )
    (net (code "70") (name "/DRAM_DQM2") (class "Default")
      (node (ref "U1") (pin "D4") (pinfunction "PI4_D4") (pintype "passive"))
      (node (ref "U2") (pin "F8") (pinfunction "DQM2_F8") (pintype "passive"))
    )
    (net (code "71") (name "/DRAM_DQM3") (class "Default")
      (node (ref "U1") (pin "C4") (pinfunction "PI5_C4") (pintype "passive"))
      (node (ref "U2") (pin "F2") (pinfunction "DQM3_F2") (pintype "passive"))
    )
    (net (code "72") (name "/DRAM_RAS") (class "Default")
      (node (ref "U1") (pin "R6") (pinfunction "PF11/DCMI_12/SPI5_MOSI/FMC_SDNRAS_R6") (pintype "passive"))
      (node (ref "U2") (pin "J9") (pinfunction "~{RAS}_J9") (pintype "passive"))
    )
    (net (code "73") (name "/DRAM_WE") (class "Default")
      (node (ref "U1") (pin "R3") (pinfunction "PA7/SPI1_MOSI/TIM8_CH1N/TIM14_CH1/TIM3_CH2/ETH_MII_RX_DV/ETH_RMII_CRS_DV_R3") (pintype "passive"))
      (node (ref "U2") (pin "K8") (pinfunction "~{WE}_K8") (pintype "passive"))
    )
    (net (code "74") (name "/FLASH_CLK") (class "Default")
      (node (ref "U1") (pin "L1") (pinfunction "PF10/FMC_INTR/DCMI_D11/LCD_DE_L1") (pintype "passive"))
      (node (ref "U6") (pin "6") (pinfunction "CLK_6") (pintype "passive"))
    )
    (net (code "75") (name "/FLASH_CS") (class "Default")
      (node (ref "R15") (pin "1") (pinfunction "1_1") (pintype "passive"))
      (node (ref "U1") (pin "J15") (pinfunction "PG6/FSMC_INT2/DCMI_D12_J15") (pintype "passive"))
      (node (ref "U6") (pin "1") (pinfunction "~{CS}_1") (pintype "passive"))
    )
    (net (code "76") (name "/FLASH_IO0") (class "Default")
      (node (ref "U1") (pin "L3") (pinfunction "PF8/TIM13_CH1/SPI5_MISO/SAI1_SCK_B/FMC_NIOWR_L3") (pintype "passive"))
      (node (ref "U6") (pin "5") (pinfunction "DI_5") (pintype "passive"))
    )
    (net (code "77") (name "/FLASH_IO1") (class "Default")
      (node (ref "U1") (pin "L2") (pinfunction "PF9/TIM14_CH1/SPI5_MOSI/SAI1_FS_B/FMC_CD_L2") (pintype "passive"))
      (node (ref "U6") (pin "2") (pinfunction "DO_2") (pintype "passive"))
    )
    (net (code "78") (name "/FLASH_IO2") (class "Default")
      (node (ref "U1") (pin "K1") (pinfunction "PF7/TIM11_CH1/SPI5_SCK/SAI1_MCLK_B/UART7_TX/FMC_NREG_K1") (pintype "passive"))
      (node (ref "U6") (pin "3") (pinfunction "~{WP}_3") (pintype "passive"))
    )
    (net (code "79") (name "/FLASH_IO3") (class "Default")
      (node (ref "U1") (pin "K2") (pinfunction "PF6/TIM10_CH1/SPI5_NSS/SAI1_SD_B/UART7_RX/FMC_NIORD_K2") (pintype "passive"))
      (node (ref "U6") (pin "7") (pinfunction "~{HOLD}/~{RESET}_7") (pintype "passive"))
    )
    (net (code "80") (name "/FS_DM") (class "Default")
      (node (ref "U1") (pin "C15") (pinfunction "PA11/TIM1_CH4/USART1_CTS/CAN1_RX/LCD_R4/OTG_FS_DM_C15") (pintype "passive"))
      (node (ref "U5") (pin "6") (pinfunction "6_6") (pintype "passive"))
    )
    (net (code "81") (name "/FS_DP") (class "Default")
      (node (ref "U1") (pin "B15") (pinfunction "PA12/TIM1_ETR/USART1_RTS/CAN1_TX/LCD_R5/OTG_FS_DP_B15") (pintype "passive"))
      (node (ref "U5") (pin "4") (pinfunction "4_4") (pintype "passive"))
    )
    (net (code "82") (name "/I2C1_SCL") (class "Default")
      (node (ref "R6") (pin "2") (pinfunction "2_2") (pintype "passive"))
      (node (ref "U1") (pin "A5") (pinfunction "PB8/TIM4_CH3/TIM10_CH1/I2C1_SCL/CAN1_RX/SDIO_D4/DCMI_D6_A5") (pintype "passive"))
      (node (ref "X3") (pin "32") (pinfunction "32_32") (pintype "passive"))
    )
    (net (code "83") (name "/I2C1_SDA") (class "Default")
      (node (ref "R7") (pin "2") (pinfunction "2_2") (pintype "passive"))
      (node (ref "U1") (pin "B4") (pinfunction "PB9/TIM11_CH1/I2C1_SDA/SPI2_NSS/I2S2_WS/SDIO_D5/DCMI_D7_B4") (pintype "passive"))
      (node (ref "X3") (pin "34") (pinfunction "34_34") (pintype "passive"))
    )
    (net (code "84") (name "/I2C2_SCL") (class "Default")
      (node (ref "JP1") (pin "5") (pinfunction "5_5") (pintype "passive"))
      (node (ref "U1") (pin "R12") (pinfunction "PB10/SPI2_SCK/I2S2_CK/I2C2_SCL/USART3_TX/OTG_HS_ULPI_D3/TIM2_CH3_R12") (pintype "passive"))
    )
    (net (code "85") (name "/I2C2_SDA") (class "Default")
      (node (ref "JP1") (pin "6") (pinfunction "6_6") (pintype "passive"))
      (node (ref "U1") (pin "R13") (pinfunction "PB11/I2C2_SDA/USART3_RX/OTG_HS_ULPI_D4/ETH_RMII_TX_EN/TIM2_CH4_R13") (pintype "passive"))
    )
    (net (code "86") (name "/LED_B") (class "Default")
      (node (ref "RN3") (pin "1") (pinfunction "1_1") (pintype "passive"))
      (node (ref "U1") (pin "M4") (pinfunction "PC2/SPI2_MISO/I2S2EXT_SD/OTG_HS_ULPI_DIR/ETH_MII_TXD2/FMC_SDNE0_M4") (pintype "passive"))
    )
    (net (code "87") (name "/LED_G") (class "Default")
      (node (ref "RN3") (pin "2") (pinfunction "2_2") (pintype "passive"))
      (node (ref "U1") (pin "M3") (pinfunction "PC1/ETH_MDC/ADC123_IN11_M3") (pintype "passive"))
    )
    (net (code "88") (name "/LED_IR") (class "Default")
      (node (ref "RN3") (pin "4") (pinfunction "4_4") (pintype "passive"))
      (node (ref "U1") (pin "A2") (pinfunction "PE2/TRACECLK/FSMC_A23/ETH_MII_TXD3/SPI4_SCK_A2") (pintype "passive"))
    )
    (net (code "89") (name "/LED_R") (class "Default")
      (node (ref "RN3") (pin "3") (pinfunction "3_3") (pintype "passive"))
      (node (ref "U1") (pin "M2") (pinfunction "PC0/OTG_HS_ULPI_STP/ADC123_IN10/FMC_SDNWE_M2") (pintype "passive"))
    )
    (net (code "90") (name "/NRST") (class "Default")
      (node (ref "C15") (pin "1") (pinfunction "1_1") (pintype "passive"))
      (node (ref "JP2") (pin "1") (pinfunction "1_1") (pintype "passive"))
      (node (ref "JP3") (pin "4") (pinfunction "4_4") (pintype "passive"))
      (node (ref "R13") (pin "1") (pinfunction "1_1") (pintype "passive"))
      (node (ref "U1") (pin "J1") (pinfunction "NRST_J1") (pintype "passive"))
    )
    (net (code "91") (name "/P9") (class "Default")
      (node (ref "JP2") (pin "4") (pinfunction "4_4") (pintype "passive"))
      (node (ref "U1") (pin "K15") (pinfunction "PG3/FMC_A13_K15") (pintype "passive"))
    )
    (net (code "92") (name "/SDIO_CLK") (class "Default")
      (node (ref "U1") (pin "A12") (pinfunction "PC12/UART5_TX/SDIO_CK/DCMI_D9/SPI3_MOSI/I2S3_SD/USART3_CK_A12") (pintype "passive"))
      (node (ref "X2") (pin "P$5") (pinfunction "CLK_P$5") (pintype "passive"))
    )
    (net (code "93") (name "/SDIO_CMD") (class "Default")
      (node (ref "R11") (pin "2") (pinfunction "2_2") (pintype "passive"))
      (node (ref "U1") (pin "D12") (pinfunction "PD2/TIM3_ETR/UART5_RX/SDIO_CMD/DCMI_D11_D12") (pintype "passive"))
      (node (ref "X2") (pin "P$3") (pinfunction "CMD_P$3") (pintype "passive"))
    )
    (net (code "94") (name "/SDIO_D0") (class "Default")
      (node (ref "RN4") (pin "8") (pinfunction "8_8") (pintype "passive"))
      (node (ref "U1") (pin "G14") (pinfunction "PC8/TIM8_CH3/SDIO_D0/TIM3_CH3/USART6_CK/DCMI_D2_G14") (pintype "passive"))
      (node (ref "X2") (pin "P$7") (pinfunction "DAT0_P$7") (pintype "passive"))
    )
    (net (code "95") (name "/SDIO_D1") (class "Default")
      (node (ref "RN4") (pin "7") (pinfunction "7_7") (pintype "passive"))
      (node (ref "U1") (pin "F14") (pinfunction "PC9/I2S_CKIN/MCO2/TIM8_CH4/SDIO_D1/I2C3_SDA/DCMI_D3/TIM3_CH4_F14") (pintype "passive"))
      (node (ref "X2") (pin "P$8") (pinfunction "DAT1_P$8") (pintype "passive"))
    )
    (net (code "96") (name "/SDIO_D2") (class "Default")
      (node (ref "RN4") (pin "6") (pinfunction "6_6") (pintype "passive"))
      (node (ref "U1") (pin "B14") (pinfunction "PC10/SPI3_SCK/I2S3_CK/UART4_TX/SDIO_D2/DCMI_D8/USART3_TX_B14") (pintype "passive"))
      (node (ref "X2") (pin "P$1") (pinfunction "DAT2_P$1") (pintype "passive"))
    )
    (net (code "97") (name "/SDIO_D3") (class "Default")
      (node (ref "RN4") (pin "5") (pinfunction "5_5") (pintype "passive"))
      (node (ref "U1") (pin "B13") (pinfunction "PC11/UART4_RX/SPI3_MISO/SDIO_D3/DCMI_D4_B13") (pintype "passive"))
      (node (ref "X2") (pin "P$2") (pinfunction "DAT3/CD_P$2") (pintype "passive"))
    )
    (net (code "98") (name "/SD_CD") (class "Default")
      (node (ref "R10") (pin "2") (pinfunction "2_2") (pintype "passive"))
      (node (ref "U1") (pin "J14") (pinfunction "PG7/FSMC_INT3/DCMI_D13_J14") (pintype "passive"))
      (node (ref "X2") (pin "CD$1") (pinfunction "CD_CD$1") (pintype "passive"))
    )
    (net (code "99") (name "/SPI2_MISO") (class "Default")
      (node (ref "JP1") (pin "2") (pinfunction "2_2") (pintype "passive"))
      (node (ref "U1") (pin "R14") (pinfunction "PB14/SPI2_MISO/TIM1_CH2N/TIM12_CH1/OTG_HS_DM/USART3_RTS/TIM8_CH2N_R14") (pintype "passive"))
    )
    (net (code "100") (name "/SPI2_MOSI") (class "Default")
      (node (ref "JP1") (pin "1") (pinfunction "1_1") (pintype "passive"))
      (node (ref "U1") (pin "R15") (pinfunction "PB15/SPI2_MOSI/I2S2_SD/TIM1_CH3N/TIM8_CH3N/TIM12_CH2/OTG_HS_DP_R15") (pintype "passive"))
    )
    (net (code "101") (name "/SPI2_NSS") (class "Default")
      (node (ref "JP1") (pin "4") (pinfunction "4_4") (pintype "passive"))
      (node (ref "U1") (pin "P12") (pinfunction "PB12/SPI2_NSS/I2S2_WS/I2C2_SMBA/USART3_CK/TIM1_BKIN/CAN2_RX_P12") (pintype "passive"))
    )
    (net (code "102") (name "/SPI2_SCLK") (class "Default")
      (node (ref "JP1") (pin "3") (pinfunction "3_3") (pintype "passive"))
      (node (ref "U1") (pin "P13") (pinfunction "PB13/SPI2_SCK/I2S2_CK/USART3_CTS/TIM1_CH1N/CAN2_TX/OTG_HS_ULPI_D6_P13") (pintype "passive"))
    )
    (net (code "103") (name "/SPI3_MISO") (class "Default")
      (node (ref "U1") (pin "A9") (pinfunction "PB4/NJTRST/TIM3_CH1/SPI1_MISO/SPI3_MISO/I2S3EXT_SD_A9") (pintype "passive"))
      (node (ref "X3") (pin "15") (pinfunction "15_15") (pintype "passive"))
    )
    (net (code "104") (name "/SPI3_MOSI") (class "Default")
      (node (ref "U1") (pin "A6") (pinfunction "PB5/TIM3_CH2/SPI1_MOSI/SPI3_MOSI/I2S3_SD/DCMI_D10/FMC_SDCKE1_A6") (pintype "passive"))
      (node (ref "X3") (pin "17") (pinfunction "17_17") (pintype "passive"))
    )
    (net (code "105") (name "/SPI3_SCLK{slash}TRACESWO") (class "Default")
      (node (ref "JP3") (pin "1") (pinfunction "1_1") (pintype "passive"))
      (node (ref "U1") (pin "A10") (pinfunction "PB3/JTDO/TRACESWO/SPI3_SCK/I2S3_CK/TIM2_CH2/SPI1_SCK_A10") (pintype "passive"))
      (node (ref "X3") (pin "13") (pinfunction "13_13") (pintype "passive"))
    )
    (net (code "106") (name "/SPI3_SSEL") (class "Default")
      (node (ref "U1") (pin "A13") (pinfunction "PA15/JTDI/SPI3_NSS/I2S3_WS/TIM2_CH1_ETR/SPI1_NSS_A13") (pintype "passive"))
      (node (ref "X3") (pin "11") (pinfunction "11_11") (pintype "passive"))
    )
    (net (code "107") (name "/SW") (class "Default")
      (node (ref "L1") (pin "1") (pinfunction "1_1") (pintype "passive"))
      (node (ref "U8") (pin "5") (pinfunction "SW_5") (pintype "power_in"))
    )
    (net (code "108") (name "/SWCLK") (class "Default")
      (node (ref "JP3") (pin "2") (pinfunction "2_2") (pintype "passive"))
      (node (ref "U1") (pin "A14") (pinfunction "PA14/JTCK-SWCLK_A14") (pintype "passive"))
    )
    (net (code "109") (name "/SWDIO") (class "Default")
      (node (ref "JP3") (pin "3") (pinfunction "3_3") (pintype "passive"))
      (node (ref "U1") (pin "A15") (pinfunction "PA13/JTMS-SWDIO_A15") (pintype "passive"))
    )
    (net (code "110") (name "/TIM4_CH1") (class "Default")
      (node (ref "JP2") (pin "6") (pinfunction "6_6") (pintype "passive"))
      (node (ref "U1") (pin "N13") (pinfunction "PD12/FMC_A17/TIM4_CH1/USART3_RTS_N13") (pintype "passive"))
    )
    (net (code "111") (name "/TIM4_CH2") (class "Default")
      (node (ref "JP2") (pin "5") (pinfunction "5_5") (pintype "passive"))
      (node (ref "U1") (pin "M15") (pinfunction "PD13/FMC_A18/TIM4_CH2_M15") (pintype "passive"))
    )
    (net (code "112") (name "/VCAP1") (class "Default")
      (node (ref "C12") (pin "1") (pinfunction "1_1") (pintype "passive"))
      (node (ref "U1") (pin "M10") (pinfunction "VCAP1_M10") (pintype "passive"))
    )
    (net (code "113") (name "/VCAP2") (class "Default")
      (node (ref "C11") (pin "1") (pinfunction "1_1") (pintype "passive"))
      (node (ref "U1") (pin "F13") (pinfunction "VCAP2_F13") (pintype "passive"))
    )
    (net (code "114") (name "GND") (class "Default")
      (node (ref "C1") (pin "1") (pinfunction "1_1") (pintype "passive"))
      (node (ref "C10") (pin "1") (pinfunction "1_1") (pintype "passive"))
      (node (ref "C11") (pin "2") (pinfunction "2_2") (pintype "passive"))
      (node (ref "C12") (pin "2") (pinfunction "2_2") (pintype "passive"))
      (node (ref "C13") (pin "2") (pinfunction "2_2") (pintype "passive"))
      (node (ref "C14") (pin "2") (pinfunction "2_2") (pintype "passive"))
      (node (ref "C15") (pin "2") (pinfunction "2_2") (pintype "passive"))
      (node (ref "C16") (pin "C") (pinfunction "-_C") (pintype "passive"))
      (node (ref "C17") (pin "2") (pinfunction "2_2") (pintype "passive"))
      (node (ref "C18") (pin "2") (pinfunction "2_2") (pintype "passive"))
      (node (ref "C19") (pin "2") (pinfunction "2_2") (pintype "passive"))
      (node (ref "C2") (pin "1") (pinfunction "1_1") (pintype "passive"))
      (node (ref "C20") (pin "2") (pinfunction "2_2") (pintype "passive"))
      (node (ref "C21") (pin "2") (pinfunction "2_2") (pintype "passive"))
      (node (ref "C22") (pin "2") (pinfunction "2_2") (pintype "passive"))
      (node (ref "C23") (pin "2") (pinfunction "2_2") (pintype "passive"))
      (node (ref "C24") (pin "2") (pinfunction "2_2") (pintype "passive"))
      (node (ref "C25") (pin "2") (pinfunction "2_2") (pintype "passive"))
      (node (ref "C26") (pin "2") (pinfunction "2_2") (pintype "passive"))
      (node (ref "C27") (pin "2") (pinfunction "2_2") (pintype "passive"))
      (node (ref "C28") (pin "2") (pinfunction "2_2") (pintype "passive"))
      (node (ref "C29") (pin "2") (pinfunction "2_2") (pintype "passive"))
      (node (ref "C3") (pin "1") (pinfunction "1_1") (pintype "passive"))
      (node (ref "C30") (pin "2") (pinfunction "2_2") (pintype "passive"))
      (node (ref "C4") (pin "1") (pinfunction "1_1") (pintype "passive"))
      (node (ref "C5") (pin "1") (pinfunction "1_1") (pintype "passive"))
      (node (ref "C6") (pin "C") (pinfunction "-_C") (pintype "passive"))
      (node (ref "C7") (pin "C") (pinfunction "-_C") (pintype "passive"))
      (node (ref "C8") (pin "2") (pinfunction "2_2") (pintype "passive"))
      (node (ref "C9") (pin "1") (pinfunction "1_1") (pintype "passive"))
      (node (ref "JP2") (pin "8") (pinfunction "8_8") (pintype "passive"))
      (node (ref "JP3") (pin "6") (pinfunction "6_6") (pintype "passive"))
      (node (ref "Q1") (pin "2") (pinfunction "S_2") (pintype "passive"))
      (node (ref "R1") (pin "1") (pinfunction "1_1") (pintype "passive"))
      (node (ref "R12") (pin "1") (pinfunction "1_1") (pintype "passive"))
      (node (ref "R3") (pin "1") (pinfunction "1_1") (pintype "passive"))
      (node (ref "R4") (pin "1") (pinfunction "1_1") (pintype "passive"))
      (node (ref "U1") (pin "D5") (pinfunction "VSS_D5") (pintype "passive"))
      (node (ref "U1") (pin "D7") (pinfunction "VSS_D7") (pintype "passive"))
      (node (ref "U1") (pin "D8") (pinfunction "VSS_D8") (pintype "passive"))
      (node (ref "U1") (pin "D9") (pinfunction "VSS_D9") (pintype "passive"))
      (node (ref "U1") (pin "F10") (pinfunction "VSS_F10") (pintype "passive"))
      (node (ref "U1") (pin "F12") (pinfunction "VSS_F12") (pintype "passive"))
      (node (ref "U1") (pin "F2") (pinfunction "VSS_F2") (pintype "passive"))
      (node (ref "U1") (pin "F6") (pinfunction "VSS_F6") (pintype "passive"))
      (node (ref "U1") (pin "F7") (pinfunction "VSS_F7") (pintype "passive"))
      (node (ref "U1") (pin "F8") (pinfunction "VSS_F8") (pintype "passive"))
      (node (ref "U1") (pin "F9") (pinfunction "VSS_F9") (pintype "passive"))
      (node (ref "U1") (pin "G10") (pinfunction "VSS_G10") (pintype "passive"))
      (node (ref "U1") (pin "G12") (pinfunction "VSS_G12") (pintype "passive"))
      (node (ref "U1") (pin "G2") (pinfunction "VSS_G2") (pintype "passive"))
      (node (ref "U1") (pin "G6") (pinfunction "VSS_G6") (pintype "passive"))
      (node (ref "U1") (pin "G7") (pinfunction "VSS_G7") (pintype "passive"))
      (node (ref "U1") (pin "G8") (pinfunction "VSS_G8") (pintype "passive"))
      (node (ref "U1") (pin "G9") (pinfunction "VSS_G9") (pintype "passive"))
      (node (ref "U1") (pin "H10") (pinfunction "VSS_H10") (pintype "passive"))
      (node (ref "U1") (pin "H12") (pinfunction "VSS_H12") (pintype "passive"))
      (node (ref "U1") (pin "H6") (pinfunction "VSS_H6") (pintype "passive"))
      (node (ref "U1") (pin "H7") (pinfunction "VSS_H7") (pintype "passive"))
      (node (ref "U1") (pin "H8") (pinfunction "VSS_H8") (pintype "passive"))
      (node (ref "U1") (pin "H9") (pinfunction "VSS_H9") (pintype "passive"))
      (node (ref "U1") (pin "J10") (pinfunction "VSS_J10") (pintype "passive"))
      (node (ref "U1") (pin "J6") (pinfunction "VSS_J6") (pintype "passive"))
      (node (ref "U1") (pin "J7") (pinfunction "VSS_J7") (pintype "passive"))
      (node (ref "U1") (pin "J8") (pinfunction "VSS_J8") (pintype "passive"))
      (node (ref "U1") (pin "J9") (pinfunction "VSS_J9") (pintype "passive"))
      (node (ref "U1") (pin "K10") (pinfunction "VSS_K10") (pintype "passive"))
      (node (ref "U1") (pin "K6") (pinfunction "VSS_K6") (pintype "passive"))
      (node (ref "U1") (pin "K7") (pinfunction "VSS_K7") (pintype "passive"))
      (node (ref "U1") (pin "K8") (pinfunction "VSS_K8") (pintype "passive"))
      (node (ref "U1") (pin "K9") (pinfunction "VSS_K9") (pintype "passive"))
      (node (ref "U1") (pin "L4") (pinfunction "VSS_L4") (pintype "passive"))
      (node (ref "U1") (pin "M1") (pinfunction "VSSA_M1") (pintype "passive"))
      (node (ref "U1") (pin "M8") (pinfunction "VSS_M8") (pintype "passive"))
      (node (ref "U1") (pin "M9") (pinfunction "VSS_M9") (pintype "passive"))
      (node (ref "U1") (pin "N1") (pinfunction "VREF-_N1") (pintype "passive"))
      (node (ref "U2") (pin "A3") (pinfunction "VSS_A3") (pintype "passive"))
      (node (ref "U2") (pin "B3") (pinfunction "VSSQ_B3") (pintype "passive"))
      (node (ref "U2") (pin "B8") (pinfunction "VSSQ_B8") (pintype "passive"))
      (node (ref "U2") (pin "C1") (pinfunction "VSSQ_C1") (pintype "passive"))
      (node (ref "U2") (pin "D1") (pinfunction "VSSQ_D1") (pintype "passive"))
      (node (ref "U2") (pin "E9") (pinfunction "VSSQ_E9") (pintype "passive"))
      (node (ref "U2") (pin "F1") (pinfunction "VSS_F1") (pintype "passive"))
      (node (ref "U2") (pin "L3") (pinfunction "VSS_L3") (pintype "passive"))
      (node (ref "U2") (pin "L9") (pinfunction "VSSQ_L9") (pintype "passive"))
      (node (ref "U2") (pin "M1") (pinfunction "VSSQ_M1") (pintype "passive"))
      (node (ref "U2") (pin "N1") (pinfunction "VSSQ_N1") (pintype "passive"))
      (node (ref "U2") (pin "P3") (pinfunction "VSSQ_P3") (pintype "passive"))
      (node (ref "U2") (pin "P8") (pinfunction "VSSQ_P8") (pintype "passive"))
      (node (ref "U2") (pin "R3") (pinfunction "VSS_R3") (pintype "passive"))
      (node (ref "U3") (pin "2") (pinfunction "VSS_2") (pintype "passive"))
      (node (ref "U5") (pin "2") (pinfunction "2_2") (pintype "passive"))
      (node (ref "U6") (pin "4") (pinfunction "GND_4") (pintype "passive"))
      (node (ref "U8") (pin "2") (pinfunction "GND_2") (pintype "power_in"))
      (node (ref "X1") (pin "5") (pinfunction "GND_5") (pintype "power_in"))
      (node (ref "X1") (pin "S") (pinfunction "SLD_S") (pintype "passive"))
      (node (ref "X2") (pin "CD$2") (pinfunction "CD_POL_CD$2") (pintype "passive"))
      (node (ref "X2") (pin "G$1") (pinfunction "SHD_G$1") (pintype "passive"))
      (node (ref "X2") (pin "G$2") (pinfunction "SHD_G$2") (pintype "passive"))
      (node (ref "X2") (pin "G$3") (pinfunction "SHD_G$3") (pintype "passive"))
      (node (ref "X2") (pin "G$4") (pinfunction "SHD_G$4") (pintype "passive"))
      (node (ref "X2") (pin "P$6") (pinfunction "VSS_P$6") (pintype "passive"))
      (node (ref "X3") (pin "19") (pinfunction "19_19") (pintype "passive"))
      (node (ref "X3") (pin "27") (pinfunction "27_27") (pintype "passive"))
      (node (ref "X3") (pin "5") (pinfunction "5_5") (pintype "passive"))
      (node (ref "X4") (pin "2") (pinfunction "1_2") (pintype "passive"))
      (node (ref "Y2") (pin "2") (pinfunction "OSC2_2") (pintype "passive"))
      (node (ref "Y2") (pin "4") (pinfunction "OSC4_4") (pintype "passive"))
    )
    (net (code "115") (name "Net-(LED1-BLU)") (class "Default")
      (node (ref "LED1") (pin "B") (pinfunction "BLU_B") (pintype "passive"))
      (node (ref "RN3") (pin "8") (pinfunction "8_8") (pintype "passive"))
    )
    (net (code "116") (name "Net-(LED1-GRN)") (class "Default")
      (node (ref "LED1") (pin "G") (pinfunction "GRN_G") (pintype "passive"))
      (node (ref "RN3") (pin "7") (pinfunction "7_7") (pintype "passive"))
    )
    (net (code "117") (name "Net-(LED1-RED)") (class "Default")
      (node (ref "LED1") (pin "R") (pinfunction "RED_R") (pintype "passive"))
      (node (ref "RN3") (pin "6") (pinfunction "6_6") (pintype "passive"))
    )
    (net (code "118") (name "Net-(LED2-PadC)") (class "Default")
      (node (ref "LED2") (pin "C") (pinfunction "C_C") (pintype "passive"))
      (node (ref "LED3") (pin "A") (pinfunction "A_A") (pintype "passive"))
    )
    (net (code "119") (name "Net-(LED3-PadC)") (class "Default")
      (node (ref "LED3") (pin "C") (pinfunction "C_C") (pintype "passive"))
      (node (ref "R5") (pin "2") (pinfunction "2_2") (pintype "passive"))
    )
    (net (code "120") (name "Net-(Q1-D)") (class "Default")
      (node (ref "Q1") (pin "3") (pinfunction "D_3") (pintype "passive"))
      (node (ref "R5") (pin "1") (pinfunction "1_1") (pintype "passive"))
    )
    (net (code "121") (name "Net-(Q1-G)") (class "Default")
      (node (ref "Q1") (pin "1") (pinfunction "G_1") (pintype "passive"))
      (node (ref "R4") (pin "2") (pinfunction "2_2") (pintype "passive"))
      (node (ref "RN3") (pin "5") (pinfunction "5_5") (pintype "passive"))
    )
    (net (code "122") (name "Net-(U1A-PA9{slash}TIM1_CH2{slash}I2C3_SMBA{slash}USART1_TX{slash}DCMI_D0{slash}OTG_FS_VBUS)") (class "Default")
      (node (ref "R9") (pin "1") (pinfunction "1_1") (pintype "passive"))
      (node (ref "U1") (pin "E15") (pinfunction "PA9/TIM1_CH2/I2C3_SMBA/USART1_TX/DCMI_D0/OTG_FS_VBUS_E15") (pintype "passive"))
    )
    (net (code "123") (name "Net-(U1A-PH0{slash}OSC_IN)") (class "Default")
      (node (ref "C10") (pin "2") (pinfunction "2_2") (pintype "passive"))
      (node (ref "U1") (pin "G1") (pinfunction "PH0/OSC_IN_G1") (pintype "passive"))
      (node (ref "Y2") (pin "3") (pinfunction "OSC3_3") (pintype "passive"))
    )
    (net (code "124") (name "Net-(U1A-PH1{slash}OSC_OUT)") (class "Default")
      (node (ref "C9") (pin "2") (pinfunction "2_2") (pintype "passive"))
      (node (ref "U1") (pin "H1") (pinfunction "PH1/OSC_OUT_H1") (pintype "passive"))
      (node (ref "Y2") (pin "1") (pinfunction "OSC1_1") (pintype "passive"))
    )
    (net (code "125") (name "Net-(U1B-VDDA)") (class "Default")
      (node (ref "C13") (pin "1") (pinfunction "1_1") (pintype "passive"))
      (node (ref "C14") (pin "1") (pinfunction "1_1") (pintype "passive"))
      (node (ref "L2") (pin "1") (pinfunction "1_1") (pintype "passive"))
      (node (ref "U1") (pin "P1") (pinfunction "VREF+_P1") (pintype "passive"))
      (node (ref "U1") (pin "R1") (pinfunction "VDDA_R1") (pintype "passive"))
    )
    (net (code "126") (name "Net-(U8-VOUT{slash}FB)") (class "Default")
      (node (ref "R2") (pin "1") (pinfunction "1_1") (pintype "passive"))
      (node (ref "R3") (pin "2") (pinfunction "2_2") (pintype "passive"))
      (node (ref "U8") (pin "4") (pinfunction "VOUT/FB_4") (pintype "passive"))
    )
    (net (code "127") (name "Net-(X1-D+)") (class "Default")
      (node (ref "U5") (pin "3") (pinfunction "3_3") (pintype "passive"))
      (node (ref "X1") (pin "3") (pinfunction "D+_3") (pintype "passive"))
    )
    (net (code "128") (name "Net-(X1-D-)") (class "Default")
      (node (ref "U5") (pin "1") (pinfunction "1_1") (pintype "passive"))
      (node (ref "X1") (pin "2") (pinfunction "D-_2") (pintype "passive"))
    )
    (net (code "129") (name "RAW") (class "Default")
      (node (ref "C2") (pin "2") (pinfunction "2_2") (pintype "passive"))
      (node (ref "D1") (pin "1") (pinfunction "C_1") (pintype "passive"))
      (node (ref "Q2") (pin "2") (pinfunction "S_2") (pintype "passive"))
      (node (ref "U8") (pin "1") (pinfunction "VIN_1") (pintype "power_in"))
      (node (ref "U8") (pin "3") (pinfunction "EN_3") (pintype "passive"))
    )
    (net (code "130") (name "VBUS") (class "Default")
      (node (ref "C1") (pin "2") (pinfunction "2_2") (pintype "passive"))
      (node (ref "Q2") (pin "3") (pinfunction "D_3") (pintype "passive"))
      (node (ref "R9") (pin "2") (pinfunction "2_2") (pintype "passive"))
      (node (ref "U5") (pin "5") (pinfunction "5_5") (pintype "passive"))
      (node (ref "X1") (pin "1") (pinfunction "5V_1") (pintype "power_in"))
    )
    (net (code "131") (name "VCC") (class "Default")
      (node (ref "C16") (pin "A") (pinfunction "+_A") (pintype "passive"))
      (node (ref "C17") (pin "1") (pinfunction "1_1") (pintype "passive"))
      (node (ref "C18") (pin "1") (pinfunction "1_1") (pintype "passive"))
      (node (ref "C19") (pin "1") (pinfunction "1_1") (pintype "passive"))
      (node (ref "C20") (pin "1") (pinfunction "1_1") (pintype "passive"))
      (node (ref "C21") (pin "1") (pinfunction "1_1") (pintype "passive"))
      (node (ref "C22") (pin "1") (pinfunction "1_1") (pintype "passive"))
      (node (ref "C23") (pin "1") (pinfunction "1_1") (pintype "passive"))
      (node (ref "C24") (pin "1") (pinfunction "1_1") (pintype "passive"))
      (node (ref "C25") (pin "1") (pinfunction "1_1") (pintype "passive"))
      (node (ref "C26") (pin "1") (pinfunction "1_1") (pintype "passive"))
      (node (ref "C27") (pin "1") (pinfunction "1_1") (pintype "passive"))
      (node (ref "C28") (pin "1") (pinfunction "1_1") (pintype "passive"))
      (node (ref "C29") (pin "1") (pinfunction "1_1") (pintype "passive"))
      (node (ref "C3") (pin "2") (pinfunction "2_2") (pintype "passive"))
      (node (ref "C30") (pin "1") (pinfunction "1_1") (pintype "passive"))
      (node (ref "C4") (pin "2") (pinfunction "2_2") (pintype "passive"))
      (node (ref "C6") (pin "A") (pinfunction "+_A") (pintype "passive"))
      (node (ref "C7") (pin "A") (pinfunction "+_A") (pintype "passive"))
      (node (ref "C8") (pin "1") (pinfunction "1_1") (pintype "passive"))
      (node (ref "JP1") (pin "8") (pinfunction "8_8") (pintype "passive"))
      (node (ref "JP3") (pin "5") (pinfunction "5_5") (pintype "passive"))
      (node (ref "L1") (pin "2") (pinfunction "2_2") (pintype "passive"))
      (node (ref "L2") (pin "2") (pinfunction "2_2") (pintype "passive"))
      (node (ref "LED1") (pin "A") (pinfunction "A_A") (pintype "passive"))
      (node (ref "LED2") (pin "A") (pinfunction "A_A") (pintype "passive"))
      (node (ref "R10") (pin "1") (pinfunction "1_1") (pintype "passive"))
      (node (ref "R11") (pin "1") (pinfunction "1_1") (pintype "passive"))
      (node (ref "R13") (pin "2") (pinfunction "2_2") (pintype "passive"))
      (node (ref "R14") (pin "2") (pinfunction "2_2") (pintype "passive"))
      (node (ref "R15") (pin "2") (pinfunction "2_2") (pintype "passive"))
      (node (ref "R2") (pin "2") (pinfunction "2_2") (pintype "passive"))
      (node (ref "R6") (pin "1") (pinfunction "1_1") (pintype "passive"))
      (node (ref "R7") (pin "1") (pinfunction "1_1") (pintype "passive"))
      (node (ref "R8") (pin "1") (pinfunction "1_1") (pintype "passive"))
      (node (ref "RN4") (pin "1") (pinfunction "1_1") (pintype "passive"))
      (node (ref "RN4") (pin "2") (pinfunction "2_2") (pintype "passive"))
      (node (ref "RN4") (pin "3") (pinfunction "3_3") (pintype "passive"))
      (node (ref "RN4") (pin "4") (pinfunction "4_4") (pintype "passive"))
      (node (ref "U1") (pin "C1") (pinfunction "VBAT_C1") (pintype "passive"))
      (node (ref "U1") (pin "C5") (pinfunction "VDD_C5") (pintype "passive"))
      (node (ref "U1") (pin "C6") (pinfunction "PDR_ON_C6") (pintype "passive"))
      (node (ref "U1") (pin "C7") (pinfunction "VDD_C7") (pintype "passive"))
      (node (ref "U1") (pin "C8") (pinfunction "VDD_C8") (pintype "passive"))
      (node (ref "U1") (pin "C9") (pinfunction "VDD_C9") (pintype "passive"))
      (node (ref "U1") (pin "F3") (pinfunction "VDD_F3") (pintype "passive"))
      (node (ref "U1") (pin "G13") (pinfunction "VDD_G13") (pintype "passive"))
      (node (ref "U1") (pin "G3") (pinfunction "VDD_G3") (pintype "passive"))
      (node (ref "U1") (pin "H13") (pinfunction "VDD33USB_H13") (pintype "passive"))
      (node (ref "U1") (pin "J12") (pinfunction "VDD_J12") (pintype "passive"))
      (node (ref "U1") (pin "J13") (pinfunction "VDD_J13") (pintype "passive"))
      (node (ref "U1") (pin "K4") (pinfunction "VDD_K4") (pintype "passive"))
      (node (ref "U1") (pin "N10") (pinfunction "VDD_N10") (pintype "passive"))
      (node (ref "U1") (pin "N8") (pinfunction "VDD_N8") (pintype "passive"))
      (node (ref "U1") (pin "N9") (pinfunction "VDD_N9") (pintype "passive"))
      (node (ref "U2") (pin "A7") (pinfunction "VDD_A7") (pintype "passive"))
      (node (ref "U2") (pin "B2") (pinfunction "VDDQ_B2") (pintype "passive"))
      (node (ref "U2") (pin "B7") (pinfunction "VDDQ_B7") (pintype "passive"))
      (node (ref "U2") (pin "C9") (pinfunction "VDDQ_C9") (pintype "passive"))
      (node (ref "U2") (pin "D9") (pinfunction "VDDQ_D9") (pintype "passive"))
      (node (ref "U2") (pin "E1") (pinfunction "VDDQ_E1") (pintype "passive"))
      (node (ref "U2") (pin "F9") (pinfunction "VDD_F9") (pintype "passive"))
      (node (ref "U2") (pin "L1") (pinfunction "VDDQ_L1") (pintype "passive"))
      (node (ref "U2") (pin "L7") (pinfunction "VDD_L7") (pintype "passive"))
      (node (ref "U2") (pin "M9") (pinfunction "VDDQ_M9") (pintype "passive"))
      (node (ref "U2") (pin "N9") (pinfunction "VDDQ_N9") (pintype "passive"))
      (node (ref "U2") (pin "P2") (pinfunction "VDDQ_P2") (pintype "passive"))
      (node (ref "U2") (pin "P7") (pinfunction "VDDQ_P7") (pintype "passive"))
      (node (ref "U2") (pin "R7") (pinfunction "VDD_R7") (pintype "passive"))
      (node (ref "U3") (pin "1") (pinfunction "VIN_1") (pintype "passive"))
      (node (ref "U3") (pin "3") (pinfunction "CE_3") (pintype "passive"))
      (node (ref "U6") (pin "8") (pinfunction "VCC_8") (pintype "passive"))
      (node (ref "X2") (pin "P$4") (pinfunction "VDD_P$4") (pintype "passive"))
      (node (ref "X3") (pin "10") (pinfunction "10_10") (pintype "passive"))
      (node (ref "X3") (pin "2") (pinfunction "2_2") (pintype "passive"))
      (node (ref "X3") (pin "20") (pinfunction "20_20") (pintype "passive"))
      (node (ref "X3") (pin "30") (pinfunction "30_30") (pintype "passive"))
      (node (ref "X3") (pin "36") (pinfunction "36_36") (pintype "passive"))
    )
    (net (code "132") (name "VDDA") (class "Default")
      (node (ref "C5") (pin "2") (pinfunction "2_2") (pintype "passive"))
      (node (ref "U3") (pin "5") (pinfunction "VOUT_5") (pintype "passive"))
      (node (ref "X3") (pin "4") (pinfunction "4_4") (pintype "passive"))
    )
    (net (code "133") (name "VIN") (class "Default")
      (node (ref "D1") (pin "2") (pinfunction "A_2") (pintype "passive"))
      (node (ref "JP2") (pin "7") (pinfunction "7_7") (pintype "passive"))
      (node (ref "Q2") (pin "1") (pinfunction "G_1") (pintype "passive"))
      (node (ref "R1") (pin "2") (pinfunction "2_2") (pintype "passive"))
      (node (ref "X4") (pin "1") (pinfunction "2_1") (pintype "passive"))
    )
    (net (code "134") (name "unconnected-(H1-MOUNT-PadB2)") (class "Default")
      (node (ref "H1") (pin "B2") (pinfunction "MOUNT_B2") (pintype "passive"))
      (node (ref "H1") (pin "8") (pinfunction "MOUNT_8") (pintype "passive"))
    )
    (net (code "135") (name "unconnected-(H2-MOUNT-PadB2)") (class "Default")
      (node (ref "H2") (pin "B2") (pinfunction "MOUNT_B2") (pintype "passive"))
      (node (ref "H2") (pin "8") (pinfunction "MOUNT_8") (pintype "passive"))
    )
    (net (code "136") (name "unconnected-(U1A-PA0{slash}USART2_CTS{slash}UART4_TX{slash}TIM2_CH1_ETR{slash}WKUP{slash}TIM5_CH1{slash}TIM8_ETR-PadN3)") (class "Default")
      (node (ref "U1") (pin "N3") (pinfunction "PA0/USART2_CTS/UART4_TX/TIM2_CH1_ETR/WKUP/TIM5_CH1/TIM8_ETR_N3") (pintype "passive+no_connect"))
    )
    (net (code "137") (name "unconnected-(U1A-PA1{slash}USART2_RTS{slash}UART4_RX{slash}TIM5_CH2{slash}TIM2_CH2-PadN2)") (class "Default")
      (node (ref "U1") (pin "N2") (pinfunction "PA1/USART2_RTS/UART4_RX/TIM5_CH2/TIM2_CH2_N2") (pintype "passive+no_connect"))
    )
    (net (code "138") (name "unconnected-(U1A-PA2{slash}USART2_TX{slash}TIM5_CH3{slash}TIM9_CH1{slash}TIM2_CH3{slash}ETH_MDIO-PadP2)") (class "Default")
      (node (ref "U1") (pin "P2") (pinfunction "PA2/USART2_TX/TIM5_CH3/TIM9_CH1/TIM2_CH3/ETH_MDIO_P2") (pintype "passive+no_connect"))
    )
    (net (code "139") (name "unconnected-(U1A-PA3{slash}USART2_RX{slash}TIM5_CH4{slash}TIM9_CH2{slash}TIM2_CH4{slash}OTG_HS_ULPI_D0-PadR2)") (class "Default")
      (node (ref "U1") (pin "R2") (pinfunction "PA3/USART2_RX/TIM5_CH4/TIM9_CH2/TIM2_CH4/OTG_HS_ULPI_D0_R2") (pintype "passive+no_connect"))
    )
    (net (code "140") (name "unconnected-(U1A-PB0{slash}TIM3_CH3{slash}TIM8_CH2N{slash}TIM1_CH2N{slash}OTG_HS_ULPI_D1{slash}ETH_MII_RXD2-PadR5)") (class "Default")
      (node (ref "U1") (pin "R5") (pinfunction "PB0/TIM3_CH3/TIM8_CH2N/TIM1_CH2N/OTG_HS_ULPI_D1/ETH_MII_RXD2_R5") (pintype "passive+no_connect"))
    )
    (net (code "141") (name "unconnected-(U1A-PB1{slash}TIM3_CH4{slash}TIM8_CH3N{slash}TIM1_CH3N{slash}OTG_HS_ULPI_D2{slash}ETH_MII_RXD3-PadR4)") (class "Default")
      (node (ref "U1") (pin "R4") (pinfunction "PB1/TIM3_CH4/TIM8_CH3N/TIM1_CH3N/OTG_HS_ULPI_D2/ETH_MII_RXD3_R4") (pintype "passive+no_connect"))
    )
    (net (code "142") (name "unconnected-(U1A-PB2{slash}BOOT1-PadM6)") (class "Default")
      (node (ref "U1") (pin "M6") (pinfunction "PB2/BOOT1_M6") (pintype "passive+no_connect"))
    )
    (net (code "143") (name "unconnected-(U1A-PC3{slash}SPI2_MOSI{slash}I2S2_SD{slash}OTG_HS_ULPI_NXT{slash}ETH_MII_TX_CLK{slash}FMC_SDCKE0-PadM5)") (class "Default")
      (node (ref "U1") (pin "M5") (pinfunction "PC3/SPI2_MOSI/I2S2_SD/OTG_HS_ULPI_NXT/ETH_MII_TX_CLK/FMC_SDCKE0_M5") (pintype "passive+no_connect"))
    )
    (net (code "144") (name "unconnected-(U1A-PC13{slash}TAMP_1-PadD1)") (class "Default")
      (node (ref "U1") (pin "D1") (pinfunction "PC13/TAMP_1_D1") (pintype "passive+no_connect"))
    )
    (net (code "145") (name "unconnected-(U1A-PC14{slash}OSC32_IN-PadE1)") (class "Default")
      (node (ref "U1") (pin "E1") (pinfunction "PC14/OSC32_IN_E1") (pintype "passive+no_connect"))
    )
    (net (code "146") (name "unconnected-(U1A-PC15{slash}OSC32_OUT-PadF1)") (class "Default")
      (node (ref "U1") (pin "F1") (pinfunction "PC15/OSC32_OUT_F1") (pintype "passive+no_connect"))
    )
    (net (code "147") (name "unconnected-(U1A-PD3{slash}SPI2_SCK{slash}I2S2_CK{slash}USART2_CTS{slash}FMC_CLK{slash}DCMI_D5-PadD11)") (class "Default")
      (node (ref "U1") (pin "D11") (pinfunction "PD3/SPI2_SCK/I2S2_CK/USART2_CTS/FMC_CLK/DCMI_D5_D11") (pintype "passive+no_connect"))
    )
    (net (code "148") (name "unconnected-(U1A-PD4{slash}USART2_RTS{slash}FMC_NOE-PadD10)") (class "Default")
      (node (ref "U1") (pin "D10") (pinfunction "PD4/USART2_RTS/FMC_NOE_D10") (pintype "passive+no_connect"))
    )
    (net (code "149") (name "unconnected-(U1A-PD5{slash}USART2_TX{slash}FMC_NWE-PadC11)") (class "Default")
      (node (ref "U1") (pin "C11") (pinfunction "PD5/USART2_TX/FMC_NWE_C11") (pintype "passive+no_connect"))
    )
    (net (code "150") (name "unconnected-(U1A-PD6{slash}SPI3_MOSI{slash}I2S3_SD{slash}USART2_RX{slash}FMC_NWAIT{slash}DCMI_D10-PadB11)") (class "Default")
      (node (ref "U1") (pin "B11") (pinfunction "PD6/SPI3_MOSI/I2S3_SD/USART2_RX/FMC_NWAIT/DCMI_D10_B11") (pintype "passive+no_connect"))
    )
    (net (code "151") (name "unconnected-(U1A-PD11{slash}FMC_A16{slash}USART3_CTS-PadN14)") (class "Default")
      (node (ref "U1") (pin "N14") (pinfunction "PD11/FMC_A16/USART3_CTS_N14") (pintype "passive+no_connect"))
    )
    (net (code "152") (name "unconnected-(U1A-PE3{slash}TRACED0{slash}FSMC_A19-PadA1)") (class "Default")
      (node (ref "U1") (pin "A1") (pinfunction "PE3/TRACED0/FSMC_A19_A1") (pintype "passive+no_connect"))
    )
    (net (code "153") (name "unconnected-(U1A-PG2{slash}FMC_A12-PadL15)") (class "Default")
      (node (ref "U1") (pin "L15") (pinfunction "PG2/FMC_A12_L15") (pintype "passive+no_connect"))
    )
    (net (code "154") (name "unconnected-(U1A-PG9{slash}USART6_RX{slash}FMC_NE2{slash}FMC_NCE3{slash}DCMI_VSYNC-PadC10)") (class "Default")
      (node (ref "U1") (pin "C10") (pinfunction "PG9/USART6_RX/FMC_NE2/FMC_NCE3/DCMI_VSYNC_C10") (pintype "passive+no_connect"))
    )
    (net (code "155") (name "unconnected-(U1A-PG12{slash}SPI6_MISO{slash}USART6_RTS{slash}LCD_B4{slash}FMC_NE4{slash}LCD_B1-PadB8)") (class "Default")
      (node (ref "U1") (pin "B8") (pinfunction "PG12/SPI6_MISO/USART6_RTS/LCD_B4/FMC_NE4/LCD_B1_B8") (pintype "passive+no_connect"))
    )
    (net (code "156") (name "unconnected-(U1A-PG13{slash}SPI6_SCK{slash}USART6_CTS{slash}ETH_MII_TXD0{slash}ETH_RMII_TXD0{slash}FMC_A24-PadA8)") (class "Default")
      (node (ref "U1") (pin "A8") (pinfunction "PG13/SPI6_SCK/USART6_CTS/ETH_MII_TXD0/ETH_RMII_TXD0/FMC_A24_A8") (pintype "passive+no_connect"))
    )
    (net (code "157") (name "unconnected-(U1A-PG14{slash}SPI6_MOSI{slash}USART6_TX{slash}ETH_MII_TXD1{slash}ETH_RMII_TXD1{slash}FMC_A25-PadA7)") (class "Default")
      (node (ref "U1") (pin "A7") (pinfunction "PG14/SPI6_MOSI/USART6_TX/ETH_MII_TXD1/ETH_RMII_TXD1/FMC_A25_A7") (pintype "passive+no_connect"))
    )
    (net (code "158") (name "unconnected-(U1A-PH2{slash}FMC_SDCKE0-PadF4)") (class "Default")
      (node (ref "U1") (pin "F4") (pinfunction "PH2/FMC_SDCKE0_F4") (pintype "passive+no_connect"))
    )
    (net (code "159") (name "unconnected-(U1A-PH3{slash}FMC_SDNE0-PadG4)") (class "Default")
      (node (ref "U1") (pin "G4") (pinfunction "PH3/FMC_SDNE0_G4") (pintype "passive+no_connect"))
    )
    (net (code "160") (name "unconnected-(U1A-PH4{slash}I2C2_SCL-PadH4)") (class "Default")
      (node (ref "U1") (pin "H4") (pinfunction "PH4/I2C2_SCL_H4") (pintype "passive+no_connect"))
    )
    (net (code "161") (name "unconnected-(U1A-PH5{slash}I2C2_SDA-PadJ4)") (class "Default")
      (node (ref "U1") (pin "J4") (pinfunction "PH5/I2C2_SDA_J4") (pintype "passive+no_connect"))
    )
    (net (code "162") (name "unconnected-(U1A-PH6-PadM11)") (class "Default")
      (node (ref "U1") (pin "M11") (pinfunction "PH6_M11") (pintype "passive+no_connect"))
    )
    (net (code "163") (name "unconnected-(U1A-PH7-PadN12)") (class "Default")
      (node (ref "U1") (pin "N12") (pinfunction "PH7_N12") (pintype "passive+no_connect"))
    )
    (net (code "164") (name "unconnected-(U1A-PI8-PadD2)") (class "Default")
      (node (ref "U1") (pin "D2") (pinfunction "PI8_D2") (pintype "passive+no_connect"))
    )
    (net (code "165") (name "unconnected-(U1A-PI11-PadE4)") (class "Default")
      (node (ref "U1") (pin "E4") (pinfunction "PI11_E4") (pintype "passive+no_connect"))
    )
    (net (code "166") (name "unconnected-(U2-NC-PadE3)") (class "Default")
      (node (ref "U2") (pin "E3") (pinfunction "NC_E3") (pintype "passive+no_connect"))
    )
    (net (code "167") (name "unconnected-(U2-NC-PadE7)") (class "Default")
      (node (ref "U2") (pin "E7") (pinfunction "NC_E7") (pintype "passive+no_connect"))
    )
    (net (code "168") (name "unconnected-(U2-NC-PadH3)") (class "Default")
      (node (ref "U2") (pin "H3") (pinfunction "NC_H3") (pintype "passive+no_connect"))
    )
    (net (code "169") (name "unconnected-(U2-NC-PadH7)") (class "Default")
      (node (ref "U2") (pin "H7") (pinfunction "NC_H7") (pintype "passive+no_connect"))
    )
    (net (code "170") (name "unconnected-(U2-NC-PadK2)") (class "Default")
      (node (ref "U2") (pin "K2") (pinfunction "NC_K2") (pintype "passive+no_connect"))
    )
    (net (code "171") (name "unconnected-(U2-NC-PadK3)") (class "Default")
      (node (ref "U2") (pin "K3") (pinfunction "NC_K3") (pintype "passive+no_connect"))
    )
    (net (code "172") (name "unconnected-(U3-NC-Pad4)") (class "Default")
      (node (ref "U3") (pin "4") (pinfunction "NC_4") (pintype "passive+no_connect"))
    )
    (net (code "173") (name "unconnected-(X1-ID-Pad4)") (class "Default")
      (node (ref "X1") (pin "4") (pinfunction "ID_4") (pintype "passive+no_connect"))
    )
    (net (code "174") (name "unconnected-(X3-Pad1)") (class "Default")
      (node (ref "X3") (pin "1") (pinfunction "1_1") (pintype "passive"))
    )
    (net (code "175") (name "unconnected-(X3-Pad3)") (class "Default")
      (node (ref "X3") (pin "3") (pinfunction "3_3") (pintype "passive"))
    )
    (net (code "176") (name "unconnected-(X3-Pad6)") (class "Default")
      (node (ref "X3") (pin "6") (pinfunction "6_6") (pintype "passive"))
    )
    (net (code "177") (name "unconnected-(X3-Pad7)") (class "Default")
      (node (ref "X3") (pin "7") (pinfunction "7_7") (pintype "passive"))
    )
    (net (code "178") (name "unconnected-(X3-Pad8)") (class "Default")
      (node (ref "X3") (pin "8") (pinfunction "8_8") (pintype "passive"))
    )
    (net (code "179") (name "unconnected-(X3-Pad9)") (class "Default")
      (node (ref "X3") (pin "9") (pinfunction "9_9") (pintype "passive"))
    )
  )
)
